# Mayfly_v1p1_revB.net
KiCad netlist of a schematic drawn in EAGLE
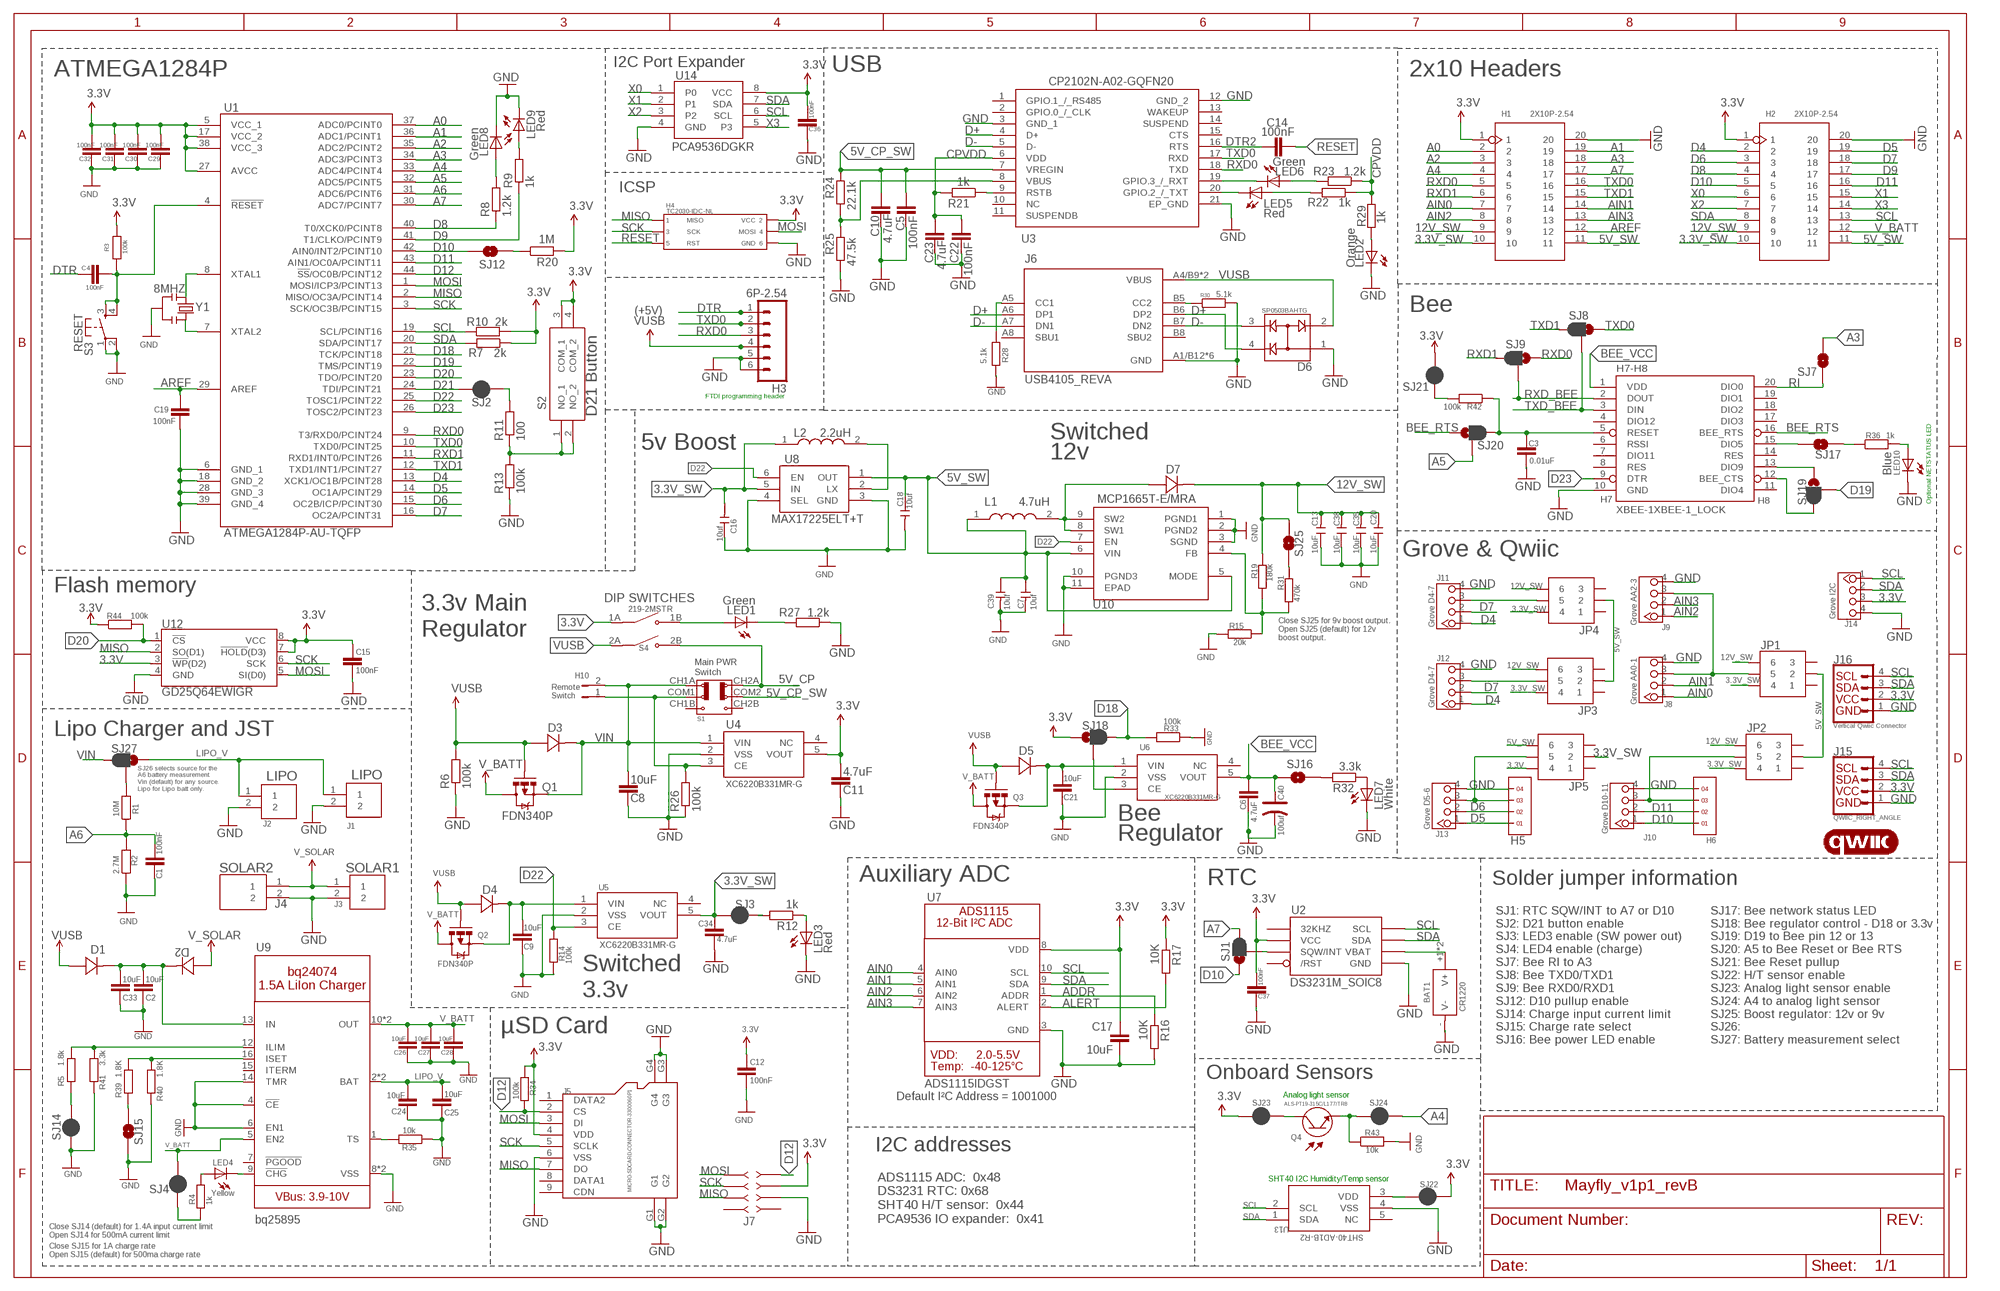
[diagram p0: schematic, sheet 1]

(export (version "E")
  (design (tool "Eeschema 10.0.6"))
  (components
    (comp (ref "BAT1")
      (value "CR1220")
      (footprint "eagle-import:BAT2P-13.5-CR1220")
      (libsource (lib "eagle-import") (part "DIP-BATTERY-CELL-HOLDER(1220)"))
    )
    (comp (ref "C1")
      (value "100nF")
      (footprint "eagle-import:C0603")
      (libsource (lib "eagle-import") (part "C_0603"))
    )
    (comp (ref "C2")
      (value "10uF")
      (footprint "eagle-import:C0603")
      (libsource (lib "eagle-import") (part "C_0603"))
    )
    (comp (ref "C3")
      (value "0.01uF")
      (footprint "eagle-import:C0603")
      (libsource (lib "eagle-import") (part "C_0603"))
    )
    (comp (ref "C4")
      (value "100nF")
      (footprint "eagle-import:C0603")
      (libsource (lib "eagle-import") (part "C_0603"))
    )
    (comp (ref "C5")
      (value "100nF")
      (footprint "eagle-import:C0603")
      (libsource (lib "eagle-import") (part "C_0603"))
    )
    (comp (ref "C6")
      (value "4.7uF")
      (footprint "eagle-import:C0603")
      (libsource (lib "eagle-import") (part "C_0603"))
    )
    (comp (ref "C7")
      (value "10uf")
      (footprint "eagle-import:C0805")
      (fields (field (name "MPN") "CC0805MKX5R5BB226"))
      (libsource (lib "eagle-import") (part "CERAMIC-22UF-6.3V-20%-X5R(0805)"))
    )
    (comp (ref "C8")
      (value "10uF")
      (footprint "eagle-import:C0603")
      (libsource (lib "eagle-import") (part "C_0603"))
    )
    (comp (ref "C9")
      (value "10uF")
      (footprint "eagle-import:C0603")
      (libsource (lib "eagle-import") (part "C_0603"))
    )
    (comp (ref "C10")
      (value "4.7uF")
      (footprint "eagle-import:C0603")
      (libsource (lib "eagle-import") (part "C_0603"))
    )
    (comp (ref "C11")
      (value "4.7uF")
      (footprint "eagle-import:C0603")
      (libsource (lib "eagle-import") (part "C_0603"))
    )
    (comp (ref "C12")
      (value "100nF")
      (footprint "eagle-import:C0603")
      (libsource (lib "eagle-import") (part "C_0603"))
    )
    (comp (ref "C13")
      (value "10uF")
      (footprint "eagle-import:C1206")
      (libsource (lib "eagle-import") (part "CERAMIC-22UF-16V-10%-X7R(1206)"))
    )
    (comp (ref "C14")
      (value "100nF")
      (footprint "eagle-import:C0603")
      (libsource (lib "eagle-import") (part "C_0603"))
    )
    (comp (ref "C15")
      (value "100nF")
      (footprint "eagle-import:C0402")
      (libsource (lib "eagle-import") (part "C_0402"))
    )
    (comp (ref "C16")
      (value "10uf")
      (footprint "eagle-import:C0603")
      (fields (field (name "MPN") "CC0603KRX5R6BB106"))
      (libsource (lib "eagle-import") (part "CERAMIC-10UF-10V-10%-X5R(0603)"))
    )
    (comp (ref "C17")
      (value "10uF")
      (footprint "eagle-import:C0603")
      (libsource (lib "eagle-import") (part "C_0603"))
    )
    (comp (ref "C18")
      (value "10uf")
      (footprint "eagle-import:C0603")
      (fields (field (name "MPN") "CC0603KRX5R6BB106"))
      (libsource (lib "eagle-import") (part "CERAMIC-10UF-10V-10%-X5R(0603)"))
    )
    (comp (ref "C19")
      (value "100nF")
      (footprint "eagle-import:C0402")
      (libsource (lib "eagle-import") (part "C_0402"))
    )
    (comp (ref "C20")
      (value "10uF")
      (footprint "eagle-import:C1206")
      (libsource (lib "eagle-import") (part "CERAMIC-22UF-16V-10%-X7R(1206)"))
    )
    (comp (ref "C21")
      (value "10uF")
      (footprint "eagle-import:C0603")
      (libsource (lib "eagle-import") (part "C_0603"))
    )
    (comp (ref "C22")
      (value "100nF")
      (footprint "eagle-import:C0603")
      (libsource (lib "eagle-import") (part "C_0603"))
    )
    (comp (ref "C23")
      (value "4.7uF")
      (footprint "eagle-import:C0603")
      (libsource (lib "eagle-import") (part "C_0603"))
    )
    (comp (ref "C24")
      (value "10uF")
      (footprint "eagle-import:C0603")
      (libsource (lib "eagle-import") (part "C_0603"))
    )
    (comp (ref "C25")
      (value "10uF")
      (footprint "eagle-import:C0603")
      (libsource (lib "eagle-import") (part "C_0603"))
    )
    (comp (ref "C26")
      (value "10uF")
      (footprint "eagle-import:C0603")
      (libsource (lib "eagle-import") (part "C_0603"))
    )
    (comp (ref "C27")
      (value "10uF")
      (footprint "eagle-import:C0603")
      (libsource (lib "eagle-import") (part "C_0603"))
    )
    (comp (ref "C28")
      (value "10uF")
      (footprint "eagle-import:C0603")
      (libsource (lib "eagle-import") (part "C_0603"))
    )
    (comp (ref "C29")
      (value "100nF")
      (footprint "eagle-import:C0603")
      (libsource (lib "eagle-import") (part "C_0603"))
    )
    (comp (ref "C30")
      (value "100nF")
      (footprint "eagle-import:C0603")
      (libsource (lib "eagle-import") (part "C_0603"))
    )
    (comp (ref "C31")
      (value "100nF")
      (footprint "eagle-import:C0603")
      (libsource (lib "eagle-import") (part "C_0603"))
    )
    (comp (ref "C32")
      (value "100nF")
      (footprint "eagle-import:C0603")
      (libsource (lib "eagle-import") (part "C_0603"))
    )
    (comp (ref "C33")
      (value "10uF")
      (footprint "eagle-import:C0603")
      (libsource (lib "eagle-import") (part "C_0603"))
    )
    (comp (ref "C34")
      (value "4.7uF")
      (footprint "eagle-import:C0603")
      (libsource (lib "eagle-import") (part "C_0603"))
    )
    (comp (ref "C35")
      (value "10uF")
      (footprint "eagle-import:C1206")
      (libsource (lib "eagle-import") (part "CERAMIC-22UF-16V-10%-X7R(1206)"))
    )
    (comp (ref "C36")
      (value "100nF")
      (footprint "eagle-import:C0603")
      (libsource (lib "eagle-import") (part "C_0603"))
    )
    (comp (ref "C37")
      (value "100nF")
      (footprint "eagle-import:C0603")
      (libsource (lib "eagle-import") (part "C_0603"))
    )
    (comp (ref "C38")
      (value "10uF")
      (footprint "eagle-import:C1206")
      (libsource (lib "eagle-import") (part "CERAMIC-22UF-16V-10%-X7R(1206)"))
    )
    (comp (ref "C39")
      (value "10uf")
      (footprint "eagle-import:C0805")
      (fields (field (name "MPN") "CC0805MKX5R5BB226"))
      (libsource (lib "eagle-import") (part "CERAMIC-22UF-6.3V-20%-X5R(0805)"))
    )
    (comp (ref "C40")
      (value "100uf")
      (footprint "eagle-import:AVX-B")
      (fields (field (name "MPN") "TAJB107M010#NJ"))
      (libsource (lib "eagle-import") (part "TANTALUM-SMD-100UF-10V(AVX-B)"))
    )
    (comp (ref "D1")
      (value "MSS2P2-M3/89A")
      (footprint "eagle-import:DIODE_MSP3V3")
      (libsource (lib "eagle-import") (part "MSS2P2-M3/89A"))
    )
    (comp (ref "D2")
      (value "MSS2P2-M3/89A")
      (footprint "eagle-import:DIODE_MSP3V3")
      (libsource (lib "eagle-import") (part "MSS2P2-M3/89A"))
    )
    (comp (ref "D3")
      (value "MSS2P2-M3/89A")
      (footprint "eagle-import:DIODE_MSP3V3")
      (libsource (lib "eagle-import") (part "MSS2P2-M3/89A"))
    )
    (comp (ref "D4")
      (value "MSS2P2-M3/89A")
      (footprint "eagle-import:DIODE_MSP3V3")
      (libsource (lib "eagle-import") (part "MSS2P2-M3/89A"))
    )
    (comp (ref "D5")
      (value "MSS2P2-M3/89A")
      (footprint "eagle-import:DIODE_MSP3V3")
      (libsource (lib "eagle-import") (part "MSS2P2-M3/89A"))
    )
    (comp (ref "D6")
      (value "SP0503BAHTG")
      (footprint "eagle-import:SOT143")
      (fields (field (name "DIGI-KEY_PART_NUMBER") "F2715CT-ND") (field (name "MF") "Littelfuse Inc."))
      (libsource (lib "eagle-import") (part "SP0503BAHTG"))
    )
    (comp (ref "D7")
      (value "MSS2P2-M3/89A")
      (footprint "eagle-import:DIODE_MSP3V3")
      (libsource (lib "eagle-import") (part "MSS2P2-M3/89A"))
    )
    (comp (ref "H1")
      (value "2X10P-2.54")
      (footprint "eagle-import:H2X10-2.54")
      (fields (field (name "MPN") "F185-1210A0BA1"))
      (libsource (lib "eagle-import") (part "DIP-BLACK-FEMALE-HEADER(2X10P-2.54)-2.54"))
    )
    (comp (ref "H2")
      (value "2X10P-2.54")
      (footprint "eagle-import:H2X10-2.54")
      (fields (field (name "MPN") "F185-1210A0BA1"))
      (libsource (lib "eagle-import") (part "DIP-BLACK-FEMALE-HEADER(2X10P-2.54)-2.54"))
    )
    (comp (ref "H3")
      (value "6P-2.54")
      (footprint "eagle-import:1X06_FEMALE_LOCK.010")
      (libsource (lib "eagle-import") (part "M06FEMALE_LOCK"))
    )
    (comp (ref "H4")
      (value "TC2030-IDC-NL")
      (footprint "eagle-import:TC2030-IDC-NL")
      (fields
        (field (name "HOUSEPART") "NO")
        (field (name "LABEL01") "MISO")
        (field (name "LABEL02") "VCC")
        (field (name "LABEL03") "SCK")
        (field (name "LABEL04") "MOSI")
        (field (name "LABEL05") "RST")
        (field (name "LABEL06") "GND")
      )
      (libsource (lib "eagle-import") (part "CON_02X03_TC2030-IDC-NL_AVRISP"))
    )
    (comp (ref "H5")
      (value "1X4")
      (footprint "eagle-import:1X4")
      (libsource (lib "eagle-import") (part "1X4"))
    )
    (comp (ref "H6")
      (value "1X4")
      (footprint "eagle-import:1X4")
      (libsource (lib "eagle-import") (part "1X4"))
    )
    (comp (ref "H7-H8")
      (value "XBEE-1XBEE-1_LOCK")
      (footprint "eagle-import:XBEE-1_LOCK")
      (libsource (lib "eagle-import") (part "XBEE-1XBEE-1_LOCK"))
    )
    (comp (ref "H10")
      (value "JUMPER-PTH-2-NO")
      (footprint "eagle-import:PTH-JUMPER-2-NO_NO_SILK")
      (libsource (lib "eagle-import") (part "JUMPER-PTH-2-NO"))
    )
    (comp (ref "J1")
      (value "JST_EPH_2PIN")
      (footprint "eagle-import:JST_EPH_B2B-PH-K-S")
      (libsource (lib "eagle-import") (part "JST_EPH_2PIN"))
    )
    (comp (ref "J2")
      (value "JST_EPH_2PIN")
      (footprint "eagle-import:JST_EPH_B2B-PH-K-S")
      (libsource (lib "eagle-import") (part "JST_EPH_2PIN"))
    )
    (comp (ref "J3")
      (value "JST_EPH_2PIN")
      (footprint "eagle-import:JST_EPH_B2B-PH-K-S")
      (libsource (lib "eagle-import") (part "JST_EPH_2PIN"))
    )
    (comp (ref "J4")
      (value "1778557")
      (footprint "eagle-import:SHDR2W70P0X250_1X2_670X500X765")
      (fields (field (name "MOUSER_PART_NUMBER") "651-1778557"))
      (libsource (lib "eagle-import") (part "1778557"))
    )
    (comp (ref "J5")
      (value "MICRO-SDCARD-CONNECTOR-3300060P1")
      (footprint "eagle-import:9P-SMD-W-RING")
      (libsource (lib "eagle-import") (part "MICRO-SDCARD-CONNECTOR-3300060P1"))
    )
    (comp (ref "J6")
      (value "USB4105_REVA")
      (footprint "eagle-import:GCT_USB4105_REVA")
      (fields (field (name "MF") "Global Connector Technology") (field (name "MP") "USB4105"))
      (libsource (lib "eagle-import") (part "USB4105_REVA"))
    )
    (comp (ref "J7")
      (value "79107-08_S")
      (footprint "eagle-import:79107-08")
      (libsource (lib "eagle-import") (part "79107-08_S"))
    )
    (comp (ref "J8")
      (value "Grove AA0-1")
      (footprint "eagle-import:HW4-2.0")
      (libsource (lib "eagle-import") (part "GROVE-CONNECTOR-DIP(4P-2.0)"))
    )
    (comp (ref "J9")
      (value "Grove AA2-3")
      (footprint "eagle-import:HW4-2.0")
      (libsource (lib "eagle-import") (part "GROVE-CONNECTOR-DIP(4P-2.0)"))
    )
    (comp (ref "J10")
      (value "Grove D10-11")
      (footprint "eagle-import:HW4-2.0")
      (libsource (lib "eagle-import") (part "GROVE-CONNECTOR-DIP(4P-2.0)"))
    )
    (comp (ref "J11")
      (value "Grove D4-7")
      (footprint "eagle-import:HW4-2.0")
      (libsource (lib "eagle-import") (part "GROVE-CONNECTOR-DIP(4P-2.0)"))
    )
    (comp (ref "J12")
      (value "Grove D4-7")
      (footprint "eagle-import:HW4-2.0")
      (libsource (lib "eagle-import") (part "GROVE-CONNECTOR-DIP(4P-2.0)"))
    )
    (comp (ref "J13")
      (value "Grove D5-6")
      (footprint "eagle-import:HW4-2.0")
      (libsource (lib "eagle-import") (part "GROVE-CONNECTOR-DIP(4P-2.0)"))
    )
    (comp (ref "J14")
      (value "Grove I2C")
      (footprint "eagle-import:HW4-2.0")
      (libsource (lib "eagle-import") (part "GROVE-CONNECTOR-DIP(4P-2.0)"))
    )
    (comp (ref "J15")
      (value "QWIIC_RIGHT_ANGLE")
      (footprint "eagle-import:JST04_1MM_RA")
      (libsource (lib "eagle-import") (part "QWIIC_CONNECTORJS-1MM"))
    )
    (comp (ref "J16")
      (value "Vertical Qwiic Connector")
      (footprint "eagle-import:JST04_1MM_VERT")
      (libsource (lib "eagle-import") (part "QWIIC_CONNECTOR"))
    )
    (comp (ref "JP1")
      (value "M22-2520305")
      (footprint "eagle-import:HDRV6W50P200_2X3_600X400X525P")
      (fields (field (name "MOUSER_PART_NUMBER") "855-M22-2520305"))
      (libsource (lib "eagle-import") (part "M22-2520305"))
    )
    (comp (ref "JP2")
      (value "M22-2520305")
      (footprint "eagle-import:HDRV6W50P200_2X3_600X400X525P")
      (fields (field (name "MOUSER_PART_NUMBER") "855-M22-2520305"))
      (libsource (lib "eagle-import") (part "M22-2520305"))
    )
    (comp (ref "JP3")
      (value "M22-2520305")
      (footprint "eagle-import:HDRV6W50P200_2X3_600X400X525P")
      (fields (field (name "MOUSER_PART_NUMBER") "855-M22-2520305"))
      (libsource (lib "eagle-import") (part "M22-2520305"))
    )
    (comp (ref "JP4")
      (value "M22-2520305")
      (footprint "eagle-import:HDRV6W50P200_2X3_600X400X525P")
      (fields (field (name "MOUSER_PART_NUMBER") "855-M22-2520305"))
      (libsource (lib "eagle-import") (part "M22-2520305"))
    )
    (comp (ref "JP5")
      (value "M22-2520305")
      (footprint "eagle-import:HDRV6W50P200_2X3_600X400X525P")
      (fields (field (name "MOUSER_PART_NUMBER") "855-M22-2520305"))
      (libsource (lib "eagle-import") (part "M22-2520305"))
    )
    (comp (ref "L1")
      (value "4.7uH")
      (footprint "eagle-import:XAL4030472MEC")
      (fields
        (field (name "MANUFACTURER_PART_NUMBER") "XAL4030-472MEC")
        (field (name "MOUSER_PART_NUMBER") "994-XAL4030-472MEC")
      )
      (libsource (lib "eagle-import") (part "XAL4030-472MEC"))
    )
    (comp (ref "L2")
      (value "2.2uH")
      (footprint "eagle-import:1285ASH1R0MP2")
      (fields
        (field (name "MANUFACTURER_PART_NUMBER") "DFE201610E-2R2M=P2")
        (field (name "MOUSER_PART_NUMBER") "81-DFE201610E-2R2MP2")
      )
      (libsource (lib "eagle-import") (part "DFE201610E-2R2M=P2"))
    )
    (comp (ref "LED1")
      (value "Green")
      (footprint "eagle-import:LED-0603")
      (libsource (lib "eagle-import") (part "LED0603"))
    )
    (comp (ref "LED2")
      (value "Orange")
      (footprint "eagle-import:LED-0603")
      (libsource (lib "eagle-import") (part "LED0603"))
    )
    (comp (ref "LED3")
      (value "Red")
      (footprint "eagle-import:LED-0603")
      (libsource (lib "eagle-import") (part "LED0603"))
    )
    (comp (ref "LED4")
      (value "Yellow")
      (footprint "eagle-import:LED-0603")
      (libsource (lib "eagle-import") (part "LED0603"))
    )
    (comp (ref "LED5")
      (value "Red")
      (footprint "eagle-import:LED-0603")
      (libsource (lib "eagle-import") (part "LED0603"))
    )
    (comp (ref "LED6")
      (value "Green")
      (footprint "eagle-import:LED-0603")
      (libsource (lib "eagle-import") (part "LED0603"))
    )
    (comp (ref "LED7")
      (value "White")
      (footprint "eagle-import:LED-0603")
      (libsource (lib "eagle-import") (part "LED0603"))
    )
    (comp (ref "LED8")
      (value "Green")
      (footprint "eagle-import:LED-0603")
      (libsource (lib "eagle-import") (part "LED0603"))
    )
    (comp (ref "LED9")
      (value "Red")
      (footprint "eagle-import:LED-0603")
      (libsource (lib "eagle-import") (part "LED0603"))
    )
    (comp (ref "LED10")
      (value "Blue")
      (footprint "eagle-import:LED-0603")
      (libsource (lib "eagle-import") (part "LED0603"))
    )
    (comp (ref "LOGO4")
      (value "QWIIC_LOGO_5MM")
      (footprint "eagle-import:QWIIC_5MM")
      (libsource (lib "eagle-import") (part "QWIIC_LOGO_5MM"))
    )
    (comp (ref "Q1")
      (value "FDN340P")
      (footprint "eagle-import:SOT23-S-PADS")
      (libsource (lib "eagle-import") (part "MOSFET-P-CHANNELSMALL"))
    )
    (comp (ref "Q2")
      (value "FDN340P")
      (footprint "eagle-import:SOT23-S-PADS")
      (libsource (lib "eagle-import") (part "MOSFET-P-CHANNELSMALL"))
    )
    (comp (ref "Q3")
      (value "FDN340P")
      (footprint "eagle-import:SOT23-S-PADS")
      (libsource (lib "eagle-import") (part "MOSFET-P-CHANNELSMALL"))
    )
    (comp (ref "Q4")
      (value "ALS-PT19-315C/L177/TR8")
      (footprint "eagle-import:XDCR_ALS-PT19-315C_L177_TR8")
      (fields (field (name "MF") "Everlight"))
      (libsource (lib "eagle-import") (part "ALS-PT19-315C/L177/TR8"))
    )
    (comp (ref "R1")
      (value "10M")
      (footprint "eagle-import:R0402")
      (libsource (lib "eagle-import") (part "R_0402"))
    )
    (comp (ref "R2")
      (value "2.7M")
      (footprint "eagle-import:R0402")
      (libsource (lib "eagle-import") (part "R_0402"))
    )
    (comp (ref "R3")
      (value "100k")
      (footprint "eagle-import:R0603")
      (libsource (lib "eagle-import") (part "R_0603"))
    )
    (comp (ref "R4")
      (value "1k")
      (footprint "eagle-import:R0402")
      (libsource (lib "eagle-import") (part "R_0402"))
    )
    (comp (ref "R5")
      (value "1.8k")
      (footprint "eagle-import:R0402")
      (libsource (lib "eagle-import") (part "R_0402"))
    )
    (comp (ref "R6")
      (value "100k")
      (footprint "eagle-import:R0402")
      (libsource (lib "eagle-import") (part "R_0402"))
    )
    (comp (ref "R7")
      (value "2k")
      (footprint "eagle-import:R0603")
      (libsource (lib "eagle-import") (part "R_0603"))
    )
    (comp (ref "R8")
      (value "1.2k")
      (footprint "eagle-import:R0402")
      (libsource (lib "eagle-import") (part "R_0402"))
    )
    (comp (ref "R9")
      (value "1k")
      (footprint "eagle-import:R0402")
      (libsource (lib "eagle-import") (part "R_0402"))
    )
    (comp (ref "R10")
      (value "2k")
      (footprint "eagle-import:R0603")
      (libsource (lib "eagle-import") (part "R_0603"))
    )
    (comp (ref "R11")
      (value "100")
      (footprint "eagle-import:R0402")
      (libsource (lib "eagle-import") (part "R_0402"))
    )
    (comp (ref "R12")
      (value "1k")
      (footprint "eagle-import:R0402")
      (libsource (lib "eagle-import") (part "R_0402"))
    )
    (comp (ref "R13")
      (value "100k")
      (footprint "eagle-import:R0402")
      (libsource (lib "eagle-import") (part "R_0402"))
    )
    (comp (ref "R14")
      (value "100k")
      (footprint "eagle-import:R0402")
      (libsource (lib "eagle-import") (part "R_0402"))
    )
    (comp (ref "R15")
      (value "20k")
      (footprint "eagle-import:R0402")
      (libsource (lib "eagle-import") (part "R_0402"))
    )
    (comp (ref "R16")
      (value "10K")
      (footprint "eagle-import:R0402")
      (libsource (lib "eagle-import") (part "R_0402"))
    )
    (comp (ref "R17")
      (value "10K")
      (footprint "eagle-import:R0402")
      (libsource (lib "eagle-import") (part "R_0402"))
    )
    (comp (ref "R19")
      (value "180k")
      (footprint "eagle-import:R0402")
      (libsource (lib "eagle-import") (part "R_0402"))
    )
    (comp (ref "R20")
      (value "1M")
      (footprint "eagle-import:R0603")
      (libsource (lib "eagle-import") (part "R_0603"))
    )
    (comp (ref "R21")
      (value "1k")
      (footprint "eagle-import:R0402")
      (libsource (lib "eagle-import") (part "R_0402"))
    )
    (comp (ref "R22")
      (value "1k")
      (footprint "eagle-import:R0402")
      (libsource (lib "eagle-import") (part "R_0402"))
    )
    (comp (ref "R23")
      (value "1.2k")
      (footprint "eagle-import:R0402")
      (libsource (lib "eagle-import") (part "R_0402"))
    )
    (comp (ref "R24")
      (value "22.1k")
      (footprint "eagle-import:R0402")
      (libsource (lib "eagle-import") (part "R_0402"))
    )
    (comp (ref "R25")
      (value "47.5k")
      (footprint "eagle-import:R0402")
      (libsource (lib "eagle-import") (part "R_0402"))
    )
    (comp (ref "R26")
      (value "100k")
      (footprint "eagle-import:R0603")
      (libsource (lib "eagle-import") (part "R_0603"))
    )
    (comp (ref "R27")
      (value "1.2k")
      (footprint "eagle-import:R0402")
      (libsource (lib "eagle-import") (part "R_0402"))
    )
    (comp (ref "R28")
      (value "5.1k")
      (footprint "eagle-import:R0402")
      (libsource (lib "eagle-import") (part "R_0402"))
    )
    (comp (ref "R29")
      (value "1k")
      (footprint "eagle-import:R0402")
      (libsource (lib "eagle-import") (part "R_0402"))
    )
    (comp (ref "R30")
      (value "5.1k")
      (footprint "eagle-import:R0402")
      (libsource (lib "eagle-import") (part "R_0402"))
    )
    (comp (ref "R31")
      (value "470k")
      (footprint "eagle-import:R0402")
      (libsource (lib "eagle-import") (part "R_0402"))
    )
    (comp (ref "R32")
      (value "3.3k")
      (footprint "eagle-import:R0402")
      (libsource (lib "eagle-import") (part "R_0402"))
    )
    (comp (ref "R33")
      (value "100k")
      (footprint "eagle-import:R0402")
      (libsource (lib "eagle-import") (part "R_0402"))
    )
    (comp (ref "R34")
      (value "100k")
      (footprint "eagle-import:R0402")
      (libsource (lib "eagle-import") (part "R_0402"))
    )
    (comp (ref "R35")
      (value "10k")
      (footprint "eagle-import:R0402")
      (libsource (lib "eagle-import") (part "R_0402"))
    )
    (comp (ref "R36")
      (value "1k")
      (footprint "eagle-import:R0402")
      (libsource (lib "eagle-import") (part "R_0402"))
    )
    (comp (ref "R39")
      (value "1.8K")
      (footprint "eagle-import:R0402")
      (libsource (lib "eagle-import") (part "R_0402"))
    )
    (comp (ref "R40")
      (value "1.8K")
      (footprint "eagle-import:R0402")
      (libsource (lib "eagle-import") (part "R_0402"))
    )
    (comp (ref "R41")
      (value "3.3k")
      (footprint "eagle-import:R0402")
      (libsource (lib "eagle-import") (part "R_0402"))
    )
    (comp (ref "R42")
      (value "100k")
      (footprint "eagle-import:R0402")
      (libsource (lib "eagle-import") (part "R_0402"))
    )
    (comp (ref "R43")
      (value "10k")
      (footprint "eagle-import:R0402")
      (libsource (lib "eagle-import") (part "R_0402"))
    )
    (comp (ref "R44")
      (value "100k")
      (footprint "eagle-import:R0402")
      (libsource (lib "eagle-import") (part "R_0402"))
    )
    (comp (ref "S1")
      (value "SWITCH-2CH-6P-3010010P1")
      (footprint "eagle-import:6P-2CH-2.54-9.1X3.5X3.2+2H")
      (libsource (lib "eagle-import") (part "SWITCH-2CH-6P-3010010P1"))
    )
    (comp (ref "S2")
      (value "PTS647SK38SMTR2LFS")
      (footprint "eagle-import:PTS647SK38SMTR2LFS")
      (fields (field (name "MOUSER_PART_NUMBER") "611-PTS647SK38SMTR2L"))
      (libsource (lib "eagle-import") (part "PTS647SK38SMTR2LFS"))
    )
    (comp (ref "S3")
      (value "MOMENTARY-SWITCH-SPST-2-SMD-4.6X2.8MM")
      (footprint "eagle-import:TACTILE_SWITCH_SMD_4.6X2.8MM")
      (libsource (lib "eagle-import") (part "MOMENTARY-SWITCH-SPST-2-SMD-4.6X2.8MM"))
    )
    (comp (ref "S4")
      (value "219-2MSTR")
      (footprint "eagle-import:SW_219-2MSTR")
      (fields (field (name "DIGI-KEY_PART_NUMBER") "CT3114CT-ND") (field (name "MF") "CTS Electrocomponents"))
      (libsource (lib "eagle-import") (part "219-2MSTR"))
    )
    (comp (ref "SJ1")
      (value "JUMPER-SMT_3_1-NC_PASTE_SILK")
      (footprint "eagle-import:SMT-JUMPER_3_1-NC_PASTE_SILK")
      (libsource (lib "eagle-import") (part "JUMPER-SMT_3_1-NC_PASTE_SILK"))
    )
    (comp (ref "SJ2")
      (value "JUMPER-SMT_2_NC_PASTE_SILK")
      (footprint "eagle-import:SMT-JUMPER_2_NC_PASTE_SILK")
      (libsource (lib "eagle-import") (part "JUMPER-SMT_2_NC_PASTE_SILK"))
    )
    (comp (ref "SJ3")
      (value "JUMPER-SMT_2_NC_PASTE_SILK")
      (footprint "eagle-import:SMT-JUMPER_2_NC_PASTE_SILK")
      (libsource (lib "eagle-import") (part "JUMPER-SMT_2_NC_PASTE_SILK"))
    )
    (comp (ref "SJ4")
      (value "JUMPER-SMT_2_NC_PASTE_SILK")
      (footprint "eagle-import:SMT-JUMPER_2_NC_PASTE_SILK")
      (libsource (lib "eagle-import") (part "JUMPER-SMT_2_NC_PASTE_SILK"))
    )
    (comp (ref "SJ7")
      (value "JUMPER-SMT_2_NO_SILK")
      (footprint "eagle-import:SMT-JUMPER_2_NO_SILK")
      (libsource (lib "eagle-import") (part "JUMPER-SMT_2_NO_SILK"))
    )
    (comp (ref "SJ8")
      (value "JUMPER-SMT_3_1-NC_PASTE_SILK")
      (footprint "eagle-import:SMT-JUMPER_3_1-NC_PASTE_SILK")
      (libsource (lib "eagle-import") (part "JUMPER-SMT_3_1-NC_PASTE_SILK"))
    )
    (comp (ref "SJ9")
      (value "JUMPER-SMT_3_1-NC_PASTE_SILK")
      (footprint "eagle-import:SMT-JUMPER_3_1-NC_PASTE_SILK")
      (libsource (lib "eagle-import") (part "JUMPER-SMT_3_1-NC_PASTE_SILK"))
    )
    (comp (ref "SJ12")
      (value "SOLDERJUMPERNO")
      (footprint "eagle-import:SJ_2S-NO")
      (libsource (lib "eagle-import") (part "SOLDERJUMPERNO"))
    )
    (comp (ref "SJ14")
      (value "JUMPER-SMT_2_NC_PASTE_SILK")
      (footprint "eagle-import:SMT-JUMPER_2_NC_PASTE_SILK")
      (libsource (lib "eagle-import") (part "JUMPER-SMT_2_NC_PASTE_SILK"))
    )
    (comp (ref "SJ15")
      (value "JUMPER-SMT_2_NO_SILK")
      (footprint "eagle-import:SMT-JUMPER_2_NO_SILK")
      (libsource (lib "eagle-import") (part "JUMPER-SMT_2_NO_SILK"))
    )
    (comp (ref "SJ16")
      (value "JUMPER-SMT_2_NO_SILK")
      (footprint "eagle-import:SMT-JUMPER_2_NO_SILK")
      (libsource (lib "eagle-import") (part "JUMPER-SMT_2_NO_SILK"))
    )
    (comp (ref "SJ17")
      (value "JUMPER-SMT_2_NO_SILK")
      (footprint "eagle-import:SMT-JUMPER_2_NO_SILK")
      (libsource (lib "eagle-import") (part "JUMPER-SMT_2_NO_SILK"))
    )
    (comp (ref "SJ18")
      (value "JUMPER-SMT_3_1-NC_PASTE_SILK")
      (footprint "eagle-import:SMT-JUMPER_3_1-NC_PASTE_SILK")
      (libsource (lib "eagle-import") (part "JUMPER-SMT_3_1-NC_PASTE_SILK"))
    )
    (comp (ref "SJ19")
      (value "JUMPER-SMT_3_1-NC_PASTE_SILK")
      (footprint "eagle-import:SMT-JUMPER_3_1-NC_PASTE_SILK")
      (libsource (lib "eagle-import") (part "JUMPER-SMT_3_1-NC_PASTE_SILK"))
    )
    (comp (ref "SJ20")
      (value "JUMPER-SMT_3_1-NC_PASTE_SILK")
      (footprint "eagle-import:SMT-JUMPER_3_1-NC_PASTE_SILK")
      (libsource (lib "eagle-import") (part "JUMPER-SMT_3_1-NC_PASTE_SILK"))
    )
    (comp (ref "SJ21")
      (value "JUMPER-SMT_2_NC_PASTE_SILK")
      (footprint "eagle-import:SMT-JUMPER_2_NC_PASTE_SILK")
      (libsource (lib "eagle-import") (part "JUMPER-SMT_2_NC_PASTE_SILK"))
    )
    (comp (ref "SJ22")
      (value "JUMPER-SMT_2_NC_PASTE_SILK")
      (footprint "eagle-import:SMT-JUMPER_2_NC_PASTE_SILK")
      (libsource (lib "eagle-import") (part "JUMPER-SMT_2_NC_PASTE_SILK"))
    )
    (comp (ref "SJ23")
      (value "JUMPER-SMT_2_NC_PASTE_SILK")
      (footprint "eagle-import:SMT-JUMPER_2_NC_PASTE_SILK")
      (libsource (lib "eagle-import") (part "JUMPER-SMT_2_NC_PASTE_SILK"))
    )
    (comp (ref "SJ24")
      (value "JUMPER-SMT_2_NC_PASTE_SILK")
      (footprint "eagle-import:SMT-JUMPER_2_NC_PASTE_SILK")
      (libsource (lib "eagle-import") (part "JUMPER-SMT_2_NC_PASTE_SILK"))
    )
    (comp (ref "SJ25")
      (value "JUMPER-SMT_2_NO_SILK")
      (footprint "eagle-import:SMT-JUMPER_2_NO_SILK")
      (libsource (lib "eagle-import") (part "JUMPER-SMT_2_NO_SILK"))
    )
    (comp (ref "SJ27")
      (value "JUMPER-SMT_3_1-NC_PASTE_SILK")
      (footprint "eagle-import:SMT-JUMPER_3_1-NC_PASTE_SILK")
      (libsource (lib "eagle-import") (part "JUMPER-SMT_3_1-NC_PASTE_SILK"))
    )
    (comp (ref "U1")
      (value "ATMEGA1284P-AU-TQFP")
      (footprint "eagle-import:QFP80P1200X1200X120-44N")
      (fields
        (field (name "MANUFACTURER_PART_NUMBER") "ATMEGA1284P-AU")
        (field (name "MOUSER_PART_NUMBER") "556-ATMEGA1284P-AU")
      )
      (libsource (lib "eagle-import") (part "ATMEGA1284P-AU-TQFP"))
    )
    (comp (ref "U2")
      (value "DS3231M_SOIC8")
      (footprint "eagle-import:SO8")
      (libsource (lib "eagle-import") (part "DS3231M_SOIC8"))
    )
    (comp (ref "U3")
      (value "CP2102N-A02-GQFN20")
      (footprint "eagle-import:CP2102NA02GQFN20")
      (fields (field (name "MOUSER_PART_NUMBER") "634-CP2102NA02GQFN20"))
      (libsource (lib "eagle-import") (part "CP2102N-A02-GQFN20"))
    )
    (comp (ref "U4")
      (value "XC6220B331MR-G")
      (footprint "eagle-import:SOT95P280X130-5N")
      (fields (field (name "MOUSER_PART_NUMBER") "865-XC6220B331MR-G"))
      (libsource (lib "eagle-import") (part "XC6220B331MR-G"))
    )
    (comp (ref "U5")
      (value "XC6220B331MR-G")
      (footprint "eagle-import:SOT95P280X130-5N")
      (fields (field (name "MOUSER_PART_NUMBER") "865-XC6220B331MR-G"))
      (libsource (lib "eagle-import") (part "XC6220B331MR-G"))
    )
    (comp (ref "U6")
      (value "XC6220B331MR-G")
      (footprint "eagle-import:SOT95P280X130-5N")
      (fields (field (name "MOUSER_PART_NUMBER") "865-XC6220B331MR-G"))
      (libsource (lib "eagle-import") (part "XC6220B331MR-G"))
    )
    (comp (ref "U7")
      (value "ADS1115IDGST")
      (footprint "eagle-import:MSOP10")
      (libsource (lib "eagle-import") (part "ADC_ADS1015"))
    )
    (comp (ref "U8")
      (value "MAX17225ELT+T")
      (footprint "eagle-import:MAX17225ELTT")
      (fields (field (name "MOUSER_PART_NUMBER") "700-MAX17225ELT+T"))
      (libsource (lib "eagle-import") (part "MAX17225ELT+T"))
    )
    (comp (ref "U9")
      (value "ADAFRUIT_POWER_BQ24074")
      (footprint "eagle-import:ADAFRUIT_POWER_QFN16_3MM")
      (libsource (lib "eagle-import") (part "ADAFRUIT_POWER_BQ24074"))
    )
    (comp (ref "U10")
      (value "MCP1665T-E/MRA")
      (footprint "eagle-import:QFN50P200X200X90-11N")
      (libsource (lib "eagle-import") (part "MCP1665T-E/MRA"))
    )
    (comp (ref "U12")
      (value "GD25Q64EWIGR")
      (footprint "eagle-import:WSON8-6X5MM")
      (libsource (lib "eagle-import") (part "W25Q32FVZP"))
    )
    (comp (ref "U13")
      (value "SHT40-AD1B-R2")
      (footprint "eagle-import:SHT4X_SEN")
      (fields (field (name "COPYRIGHT") "Copyright (C) 2018 Accelerated Designs. All rights reserved"))
      (libsource (lib "eagle-import") (part "SHT40-AD1B-R2"))
    )
    (comp (ref "U14")
      (value "PCA9536DGKR")
      (footprint "eagle-import:SOP65P490X110-8N")
      (fields (field (name "MOUSER_PART_NUMBER") "595-PCA9536DGKR"))
      (libsource (lib "eagle-import") (part "PCA9536DGKR"))
    )
    (comp (ref "Y1")
      (value "8MHZ")
      (footprint "eagle-import:X3-SMD-3.6X1.3X0.8MM")
      (fields (field (name "MPN") "CSTCE8M00G15L99-R0"))
      (libsource (lib "eagle-import") (part "SMD-RESONATOR-8MHZ-33PF-0.1%(3P-3.2X1.3MM)"))
    )
  )
  (nets
    (net (code "1") (name "/5V_CP") (class "Default")
      (node (ref "S1") (pin "CH2A") (pinfunction "CH2A_CH2A") (pintype "bidirectional"))
      (node (ref "S4") (pin "2B") (pinfunction "NO2_2B") (pintype "passive"))
    )
    (net (code "2") (name "/A0") (class "Default")
      (node (ref "H1") (pin "2") (pinfunction "2_2") (pintype "bidirectional"))
      (node (ref "U1") (pin "37") (pinfunction "ADC0/PCINT0_37") (pintype "bidirectional"))
    )
    (net (code "3") (name "/A1") (class "Default")
      (node (ref "H1") (pin "19") (pinfunction "19_19") (pintype "bidirectional"))
      (node (ref "U1") (pin "36") (pinfunction "ADC1/PCINT1_36") (pintype "bidirectional"))
    )
    (net (code "4") (name "/A2") (class "Default")
      (node (ref "H1") (pin "3") (pinfunction "3_3") (pintype "bidirectional"))
      (node (ref "U1") (pin "35") (pinfunction "ADC2/PCINT2_35") (pintype "bidirectional"))
    )
    (net (code "5") (name "/ADDR") (class "Default")
      (node (ref "R16") (pin "1") (pinfunction "1_1") (pintype "passive"))
      (node (ref "U7") (pin "1") (pinfunction "ADDR_1") (pintype "bidirectional"))
    )
    (net (code "6") (name "/AIN0") (class "Default")
      (node (ref "H1") (pin "7") (pinfunction "7_7") (pintype "bidirectional"))
      (node (ref "J8") (pin "1") (pinfunction "1_1") (pintype "bidirectional"))
      (node (ref "U7") (pin "4") (pinfunction "AIN0_4") (pintype "bidirectional"))
    )
    (net (code "7") (name "/AIN1") (class "Default")
      (node (ref "H1") (pin "14") (pinfunction "14_14") (pintype "bidirectional"))
      (node (ref "J8") (pin "2") (pinfunction "2_2") (pintype "bidirectional"))
      (node (ref "U7") (pin "5") (pinfunction "AIN1_5") (pintype "bidirectional"))
    )
    (net (code "8") (name "/AIN2") (class "Default")
      (node (ref "H1") (pin "8") (pinfunction "8_8") (pintype "bidirectional"))
      (node (ref "J9") (pin "1") (pinfunction "1_1") (pintype "bidirectional"))
      (node (ref "U7") (pin "6") (pinfunction "AIN2_6") (pintype "bidirectional"))
    )
    (net (code "9") (name "/AIN3") (class "Default")
      (node (ref "H1") (pin "13") (pinfunction "13_13") (pintype "bidirectional"))
      (node (ref "J9") (pin "2") (pinfunction "2_2") (pintype "bidirectional"))
      (node (ref "U7") (pin "7") (pinfunction "AIN3_7") (pintype "bidirectional"))
    )
    (net (code "10") (name "/ALERT") (class "Default")
      (node (ref "R17") (pin "2") (pinfunction "2_2") (pintype "passive"))
      (node (ref "U7") (pin "2") (pinfunction "ALERT_2") (pintype "bidirectional"))
    )
    (net (code "11") (name "/AREF") (class "Default")
      (node (ref "C19") (pin "2") (pinfunction "2_2") (pintype "passive"))
      (node (ref "H1") (pin "12") (pinfunction "12_12") (pintype "bidirectional"))
      (node (ref "U1") (pin "29") (pinfunction "AREF_29") (pintype "bidirectional"))
    )
    (net (code "12") (name "/BEE_RTS") (class "Default")
      (node (ref "H7-H8") (pin "16") (pinfunction "BEE_RTS_16") (pintype "input"))
      (node (ref "SJ20") (pin "1") (pinfunction "1_1") (pintype "passive"))
    )
    (net (code "13") (name "/CPVDD") (class "Default")
      (node (ref "C22") (pin "2") (pinfunction "2_2") (pintype "passive"))
      (node (ref "C23") (pin "2") (pinfunction "2_2") (pintype "passive"))
      (node (ref "R21") (pin "2") (pinfunction "2_2") (pintype "passive"))
      (node (ref "R22") (pin "1") (pinfunction "1_1") (pintype "passive"))
      (node (ref "R23") (pin "1") (pinfunction "1_1") (pintype "passive"))
      (node (ref "R29") (pin "1") (pinfunction "1_1") (pintype "passive"))
      (node (ref "U3") (pin "6") (pinfunction "VDD_6") (pintype "bidirectional"))
    )
    (net (code "14") (name "/D+") (class "Default")
      (node (ref "D6") (pin "4") (pinfunction "4_4") (pintype "passive"))
      (node (ref "J6") (pin "A6") (pinfunction "DP1_A6") (pintype "bidirectional"))
      (node (ref "J6") (pin "B6") (pinfunction "DP2_B6") (pintype "bidirectional"))
      (node (ref "U3") (pin "4") (pinfunction "D+_4") (pintype "bidirectional"))
    )
    (net (code "15") (name "/D-") (class "Default")
      (node (ref "D6") (pin "3") (pinfunction "3_3") (pintype "passive"))
      (node (ref "J6") (pin "A7") (pinfunction "DN1_A7") (pintype "bidirectional"))
      (node (ref "J6") (pin "B7") (pinfunction "DN2_B7") (pintype "bidirectional"))
      (node (ref "U3") (pin "5") (pinfunction "D-_5") (pintype "bidirectional"))
    )
    (net (code "16") (name "/D4") (class "Default")
      (node (ref "H2") (pin "2") (pinfunction "2_2") (pintype "bidirectional"))
      (node (ref "J11") (pin "1") (pinfunction "1_1") (pintype "bidirectional"))
      (node (ref "J12") (pin "1") (pinfunction "1_1") (pintype "bidirectional"))
      (node (ref "U1") (pin "13") (pinfunction "XCK1/OC1B/PCINT28_13") (pintype "bidirectional"))
    )
    (net (code "17") (name "/D5") (class "Default")
      (node (ref "H2") (pin "19") (pinfunction "19_19") (pintype "bidirectional"))
      (node (ref "H5") (pin "1") (pinfunction "1_1") (pintype "bidirectional"))
      (node (ref "J13") (pin "1") (pinfunction "1_1") (pintype "bidirectional"))
      (node (ref "U1") (pin "14") (pinfunction "OC1A/PCINT29_14") (pintype "bidirectional"))
    )
    (net (code "18") (name "/D6") (class "Default")
      (node (ref "H2") (pin "3") (pinfunction "3_3") (pintype "bidirectional"))
      (node (ref "H5") (pin "2") (pinfunction "2_2") (pintype "bidirectional"))
      (node (ref "J13") (pin "2") (pinfunction "2_2") (pintype "bidirectional"))
      (node (ref "U1") (pin "15") (pinfunction "OC2B/ICP/PCINT30_15") (pintype "bidirectional"))
    )
    (net (code "19") (name "/D7") (class "Default")
      (node (ref "H2") (pin "18") (pinfunction "18_18") (pintype "bidirectional"))
      (node (ref "J11") (pin "2") (pinfunction "2_2") (pintype "bidirectional"))
      (node (ref "J12") (pin "2") (pinfunction "2_2") (pintype "bidirectional"))
      (node (ref "U1") (pin "16") (pinfunction "OC2A/PCINT31_16") (pintype "bidirectional"))
    )
    (net (code "20") (name "/D8") (class "Default")
      (node (ref "H2") (pin "4") (pinfunction "4_4") (pintype "bidirectional"))
      (node (ref "R8") (pin "1") (pinfunction "1_1") (pintype "passive"))
      (node (ref "U1") (pin "40") (pinfunction "T0/XCK0/PCINT8_40") (pintype "bidirectional"))
    )
    (net (code "21") (name "/D9") (class "Default")
      (node (ref "H2") (pin "17") (pinfunction "17_17") (pintype "bidirectional"))
      (node (ref "R9") (pin "1") (pinfunction "1_1") (pintype "passive"))
      (node (ref "U1") (pin "41") (pinfunction "T1/CLKO/PCINT9_41") (pintype "bidirectional"))
    )
    (net (code "22") (name "/D11") (class "Default")
      (node (ref "H2") (pin "16") (pinfunction "16_16") (pintype "bidirectional"))
      (node (ref "H6") (pin "2") (pinfunction "2_2") (pintype "bidirectional"))
      (node (ref "J10") (pin "2") (pinfunction "2_2") (pintype "bidirectional"))
      (node (ref "U1") (pin "43") (pinfunction "AIN1/OC0A/PCINT11_43") (pintype "bidirectional"))
    )
    (net (code "23") (name "/D21") (class "Default")
      (node (ref "SJ2") (pin "2") (pinfunction "2_2") (pintype "passive"))
      (node (ref "U1") (pin "24") (pinfunction "TDI/PCINT21_24") (pintype "bidirectional"))
    )
    (net (code "24") (name "/DTR") (class "Default")
      (node (ref "C4") (pin "1") (pinfunction "1_1") (pintype "passive"))
      (node (ref "H3") (pin "1") (pinfunction "1_1") (pintype "passive"))
    )
    (net (code "25") (name "/DTR2") (class "Default")
      (node (ref "C14") (pin "2") (pinfunction "2_2") (pintype "passive"))
      (node (ref "U3") (pin "16") (pinfunction "RTS_16") (pintype "bidirectional"))
    )
    (net (code "26") (name "/LIPO_V") (class "Default")
      (node (ref "C24") (pin "2") (pinfunction "2_2") (pintype "passive"))
      (node (ref "C25") (pin "2") (pinfunction "2_2") (pintype "passive"))
      (node (ref "J1") (pin "1") (pinfunction "1_1") (pintype "bidirectional"))
      (node (ref "J2") (pin "1") (pinfunction "1_1") (pintype "bidirectional"))
      (node (ref "SJ27") (pin "1") (pinfunction "1_1") (pintype "passive"))
      (node (ref "U9") (pin "2") (pinfunction "BAT_2") (pintype "input"))
      (node (ref "U9") (pin "3") (pinfunction "BAT_3") (pintype "input"))
    )
    (net (code "27") (name "/MISO") (class "Default")
      (node (ref "H4") (pin "P$1") (pinfunction "PIN1_P$1") (pintype "bidirectional"))
      (node (ref "J5") (pin "7") (pinfunction "DO_7") (pintype "bidirectional"))
      (node (ref "J7") (pin "6") (pinfunction "J_6") (pintype "passive"))
      (node (ref "U1") (pin "2") (pinfunction "MISO/OC3A/PCINT14_2") (pintype "bidirectional"))
      (node (ref "U12") (pin "2") (pinfunction "SO(D1)_2") (pintype "bidirectional"))
    )
    (net (code "28") (name "/MOSI") (class "Default")
      (node (ref "H4") (pin "P$4") (pinfunction "PIN4_P$4") (pintype "bidirectional"))
      (node (ref "J5") (pin "3") (pinfunction "DI_3") (pintype "bidirectional"))
      (node (ref "J7") (pin "2") (pinfunction "J_2") (pintype "passive"))
      (node (ref "U1") (pin "1") (pinfunction "MOSI/ICP3/PCINT13_1") (pintype "bidirectional"))
      (node (ref "U12") (pin "5") (pinfunction "SI(D0)_5") (pintype "bidirectional"))
    )
    (net (code "29") (name "/RI") (class "Default")
      (node (ref "H7-H8") (pin "20") (pinfunction "DIO0_20") (pintype "bidirectional"))
      (node (ref "SJ7") (pin "1") (pinfunction "1_1") (pintype "passive"))
    )
    (net (code "30") (name "/RXD0") (class "Default")
      (node (ref "H1") (pin "5") (pinfunction "5_5") (pintype "bidirectional"))
      (node (ref "H3") (pin "3") (pinfunction "3_3") (pintype "passive"))
      (node (ref "SJ9") (pin "1") (pinfunction "1_1") (pintype "passive"))
      (node (ref "U1") (pin "9") (pinfunction "T3/RXD0/PCINT24_9") (pintype "bidirectional"))
      (node (ref "U3") (pin "18") (pinfunction "TXD_18") (pintype "bidirectional"))
    )
    (net (code "31") (name "/RXD1") (class "Default")
      (node (ref "H1") (pin "6") (pinfunction "6_6") (pintype "bidirectional"))
      (node (ref "SJ9") (pin "3") (pinfunction "3_3") (pintype "passive"))
      (node (ref "U1") (pin "11") (pinfunction "RXD1/INT0/PCINT26_11") (pintype "bidirectional"))
    )
    (net (code "32") (name "/RXD_BEE") (class "Default")
      (node (ref "H7-H8") (pin "2") (pinfunction "DOUT_2") (pintype "output"))
      (node (ref "SJ9") (pin "2") (pinfunction "2_2") (pintype "passive"))
    )
    (net (code "33") (name "/SCK") (class "Default")
      (node (ref "H4") (pin "P$3") (pinfunction "PIN3_P$3") (pintype "bidirectional"))
      (node (ref "J5") (pin "5") (pinfunction "SCLK_5") (pintype "bidirectional"))
      (node (ref "J7") (pin "4") (pinfunction "J_4") (pintype "passive"))
      (node (ref "U1") (pin "3") (pinfunction "SCK/OC3B/PCINT15_3") (pintype "bidirectional"))
      (node (ref "U12") (pin "6") (pinfunction "SCK_6") (pintype "bidirectional"))
    )
    (net (code "34") (name "/SCL") (class "Default")
      (node (ref "H2") (pin "13") (pinfunction "13_13") (pintype "bidirectional"))
      (node (ref "J14") (pin "1") (pinfunction "1_1") (pintype "bidirectional"))
      (node (ref "J15") (pin "4") (pinfunction "4_4") (pintype "passive"))
      (node (ref "J16") (pin "4") (pinfunction "4_4") (pintype "passive"))
      (node (ref "R10") (pin "1") (pinfunction "1_1") (pintype "passive"))
      (node (ref "U1") (pin "19") (pinfunction "SCL/PCINT16_19") (pintype "bidirectional"))
      (node (ref "U13") (pin "2") (pinfunction "SCL_2") (pintype "input"))
      (node (ref "U14") (pin "6") (pinfunction "SCL_6") (pintype "bidirectional"))
      (node (ref "U2") (pin "8") (pinfunction "SCL_8") (pintype "bidirectional"))
      (node (ref "U7") (pin "10") (pinfunction "SCL_10") (pintype "bidirectional"))
    )
    (net (code "35") (name "/SDA") (class "Default")
      (node (ref "H2") (pin "8") (pinfunction "8_8") (pintype "bidirectional"))
      (node (ref "J14") (pin "2") (pinfunction "2_2") (pintype "bidirectional"))
      (node (ref "J15") (pin "3") (pinfunction "3_3") (pintype "passive"))
      (node (ref "J16") (pin "3") (pinfunction "3_3") (pintype "passive"))
      (node (ref "R7") (pin "2") (pinfunction "2_2") (pintype "passive"))
      (node (ref "U1") (pin "20") (pinfunction "SDA/PCINT17_20") (pintype "bidirectional"))
      (node (ref "U13") (pin "1") (pinfunction "SDA_1") (pintype "bidirectional"))
      (node (ref "U14") (pin "7") (pinfunction "SDA_7") (pintype "bidirectional"))
      (node (ref "U2") (pin "7") (pinfunction "SDA_7") (pintype "bidirectional"))
      (node (ref "U7") (pin "9") (pinfunction "SDA_9") (pintype "bidirectional"))
    )
    (net (code "36") (name "/TXD0") (class "Default")
      (node (ref "H1") (pin "16") (pinfunction "16_16") (pintype "bidirectional"))
      (node (ref "H3") (pin "2") (pinfunction "2_2") (pintype "passive"))
      (node (ref "SJ8") (pin "1") (pinfunction "1_1") (pintype "passive"))
      (node (ref "U1") (pin "10") (pinfunction "TXD0/PCINT25_10") (pintype "bidirectional"))
      (node (ref "U3") (pin "17") (pinfunction "RXD_17") (pintype "bidirectional"))
    )
    (net (code "37") (name "/TXD1") (class "Default")
      (node (ref "H1") (pin "15") (pinfunction "15_15") (pintype "bidirectional"))
      (node (ref "SJ8") (pin "3") (pinfunction "3_3") (pintype "passive"))
      (node (ref "U1") (pin "12") (pinfunction "TXD1/INT1/PCINT27_12") (pintype "bidirectional"))
    )
    (net (code "38") (name "/TXD_BEE") (class "Default")
      (node (ref "H7-H8") (pin "3") (pinfunction "DIN_3") (pintype "input"))
      (node (ref "SJ8") (pin "2") (pinfunction "2_2") (pintype "passive"))
    )
    (net (code "39") (name "/VIN") (class "Default")
      (node (ref "C8") (pin "2") (pinfunction "2_2") (pintype "passive"))
      (node (ref "D3") (pin "1") (pinfunction "1_1") (pintype "passive"))
      (node (ref "H10") (pin "2") (pinfunction "2_2") (pintype "passive"))
      (node (ref "Q1") (pin "2") (pinfunction "S_2") (pintype "passive"))
      (node (ref "S1") (pin "CH1A") (pinfunction "CH1A_CH1A") (pintype "bidirectional"))
      (node (ref "SJ27") (pin "3") (pinfunction "3_3") (pintype "passive"))
      (node (ref "U4") (pin "1") (pinfunction "VIN_1") (pintype "bidirectional"))
    )
    (net (code "40") (name "/X0") (class "Default")
      (node (ref "H2") (pin "6") (pinfunction "6_6") (pintype "bidirectional"))
      (node (ref "U14") (pin "1") (pinfunction "P0_1") (pintype "bidirectional"))
    )
    (net (code "41") (name "/X1") (class "Default")
      (node (ref "H2") (pin "15") (pinfunction "15_15") (pintype "bidirectional"))
      (node (ref "U14") (pin "2") (pinfunction "P1_2") (pintype "bidirectional"))
    )
    (net (code "42") (name "/X2") (class "Default")
      (node (ref "H2") (pin "7") (pinfunction "7_7") (pintype "bidirectional"))
      (node (ref "U14") (pin "3") (pinfunction "P2_3") (pintype "bidirectional"))
    )
    (net (code "43") (name "/X3") (class "Default")
      (node (ref "H2") (pin "14") (pinfunction "14_14") (pintype "bidirectional"))
      (node (ref "U14") (pin "5") (pinfunction "P3_5") (pintype "bidirectional"))
    )
    (net (code "44") (name "3.3V") (class "Default")
      (node (ref "C11") (pin "2") (pinfunction "2_2") (pintype "passive"))
      (node (ref "C12") (pin "2") (pinfunction "2_2") (pintype "passive"))
      (node (ref "C15") (pin "2") (pinfunction "2_2") (pintype "passive"))
      (node (ref "C17") (pin "1") (pinfunction "1_1") (pintype "passive"))
      (node (ref "C29") (pin "2") (pinfunction "2_2") (pintype "passive"))
      (node (ref "C30") (pin "2") (pinfunction "2_2") (pintype "passive"))
      (node (ref "C31") (pin "2") (pinfunction "2_2") (pintype "passive"))
      (node (ref "C32") (pin "2") (pinfunction "2_2") (pintype "passive"))
      (node (ref "C36") (pin "2") (pinfunction "2_2") (pintype "passive"))
      (node (ref "C37") (pin "2") (pinfunction "2_2") (pintype "passive"))
      (node (ref "H1") (pin "1") (pinfunction "1_1") (pintype "bidirectional"))
      (node (ref "H2") (pin "1") (pinfunction "1_1") (pintype "bidirectional"))
      (node (ref "H4") (pin "P$2") (pinfunction "PIN2_P$2") (pintype "bidirectional"))
      (node (ref "J14") (pin "3") (pinfunction "3_3") (pintype "bidirectional"))
      (node (ref "J15") (pin "2") (pinfunction "2_2") (pintype "power_in"))
      (node (ref "J16") (pin "2") (pinfunction "2_2") (pintype "power_in"))
      (node (ref "J5") (pin "4") (pinfunction "VDD_4") (pintype "bidirectional"))
      (node (ref "J7") (pin "3") (pinfunction "J_3") (pintype "passive"))
      (node (ref "JP5") (pin "4") (pinfunction "4_4") (pintype "bidirectional"))
      (node (ref "R10") (pin "2") (pinfunction "2_2") (pintype "passive"))
      (node (ref "R17") (pin "1") (pinfunction "1_1") (pintype "passive"))
      (node (ref "R20") (pin "2") (pinfunction "2_2") (pintype "passive"))
      (node (ref "R3") (pin "2") (pinfunction "2_2") (pintype "passive"))
      (node (ref "R34") (pin "1") (pinfunction "1_1") (pintype "passive"))
      (node (ref "R44") (pin "1") (pinfunction "1_1") (pintype "passive"))
      (node (ref "R7") (pin "1") (pinfunction "1_1") (pintype "passive"))
      (node (ref "S2") (pin "3") (pinfunction "COM_1_3") (pintype "bidirectional"))
      (node (ref "S2") (pin "4") (pinfunction "COM_2_4") (pintype "bidirectional"))
      (node (ref "S4") (pin "1A") (pinfunction "COM1_1A") (pintype "passive"))
      (node (ref "SJ18") (pin "1") (pinfunction "1_1") (pintype "passive"))
      (node (ref "SJ21") (pin "2") (pinfunction "2_2") (pintype "passive"))
      (node (ref "SJ22") (pin "1") (pinfunction "1_1") (pintype "passive"))
      (node (ref "SJ23") (pin "1") (pinfunction "1_1") (pintype "passive"))
      (node (ref "U1") (pin "17") (pinfunction "VCC_2_17") (pintype "bidirectional"))
      (node (ref "U1") (pin "27") (pinfunction "AVCC_27") (pintype "bidirectional"))
      (node (ref "U1") (pin "38") (pinfunction "VCC_3_38") (pintype "bidirectional"))
      (node (ref "U1") (pin "5") (pinfunction "VCC_1_5") (pintype "bidirectional"))
      (node (ref "U12") (pin "3") (pinfunction "~{WP}(D2)_3") (pintype "bidirectional"))
      (node (ref "U12") (pin "7") (pinfunction "~{HOLD}(D3)_7") (pintype "bidirectional"))
      (node (ref "U12") (pin "8") (pinfunction "VCC_8") (pintype "bidirectional"))
      (node (ref "U14") (pin "8") (pinfunction "VCC_8") (pintype "bidirectional"))
      (node (ref "U2") (pin "2") (pinfunction "VCC_2") (pintype "bidirectional"))
      (node (ref "U4") (pin "5") (pinfunction "VOUT_5") (pintype "bidirectional"))
      (node (ref "U7") (pin "8") (pinfunction "VDD_8") (pintype "bidirectional"))
    )
    (net (code "45") (name "3.3V_SW") (class "Default")
      (node (ref "C16") (pin "2") (pinfunction "2_2") (pintype "passive"))
      (node (ref "C34") (pin "2") (pinfunction "2_2") (pintype "passive"))
      (node (ref "H1") (pin "10") (pinfunction "10_10") (pintype "bidirectional"))
      (node (ref "H2") (pin "10") (pinfunction "10_10") (pintype "bidirectional"))
      (node (ref "JP1") (pin "4") (pinfunction "4_4") (pintype "bidirectional"))
      (node (ref "JP2") (pin "4") (pinfunction "4_4") (pintype "bidirectional"))
      (node (ref "JP3") (pin "4") (pinfunction "4_4") (pintype "bidirectional"))
      (node (ref "JP4") (pin "4") (pinfunction "4_4") (pintype "bidirectional"))
      (node (ref "JP5") (pin "2") (pinfunction "2_2") (pintype "bidirectional"))
      (node (ref "L2") (pin "1") (pinfunction "1_1") (pintype "bidirectional"))
      (node (ref "SJ3") (pin "1") (pinfunction "1_1") (pintype "passive"))
      (node (ref "U5") (pin "5") (pinfunction "VOUT_5") (pintype "bidirectional"))
      (node (ref "U8") (pin "5") (pinfunction "IN_5") (pintype "bidirectional"))
    )
    (net (code "46") (name "5V_CP_SW") (class "Default")
      (node (ref "C10") (pin "2") (pinfunction "2_2") (pintype "passive"))
      (node (ref "C5") (pin "2") (pinfunction "2_2") (pintype "passive"))
      (node (ref "R24") (pin "2") (pinfunction "2_2") (pintype "passive"))
      (node (ref "S1") (pin "COM2") (pinfunction "COM2_COM2") (pintype "bidirectional"))
      (node (ref "U3") (pin "7") (pinfunction "VREGIN_7") (pintype "bidirectional"))
    )
    (net (code "47") (name "5V_SW") (class "Default")
      (node (ref "C18") (pin "1") (pinfunction "1_1") (pintype "passive"))
      (node (ref "C39") (pin "1") (pinfunction "1_1") (pintype "passive"))
      (node (ref "C7") (pin "1") (pinfunction "1_1") (pintype "passive"))
      (node (ref "H1") (pin "11") (pinfunction "11_11") (pintype "bidirectional"))
      (node (ref "H2") (pin "11") (pinfunction "11_11") (pintype "bidirectional"))
      (node (ref "JP1") (pin "2") (pinfunction "2_2") (pintype "bidirectional"))
      (node (ref "JP2") (pin "2") (pinfunction "2_2") (pintype "bidirectional"))
      (node (ref "JP3") (pin "2") (pinfunction "2_2") (pintype "bidirectional"))
      (node (ref "JP4") (pin "2") (pinfunction "2_2") (pintype "bidirectional"))
      (node (ref "JP5") (pin "6") (pinfunction "6_6") (pintype "bidirectional"))
      (node (ref "L1") (pin "1") (pinfunction "1_1") (pintype "bidirectional"))
      (node (ref "U10") (pin "5") (pinfunction "MODE_5") (pintype "bidirectional"))
      (node (ref "U10") (pin "6") (pinfunction "VIN_6") (pintype "bidirectional"))
      (node (ref "U8") (pin "1") (pinfunction "OUT_1") (pintype "bidirectional"))
    )
    (net (code "48") (name "12V_SW") (class "Default")
      (node (ref "C13") (pin "2") (pinfunction "2_2") (pintype "passive"))
      (node (ref "C20") (pin "2") (pinfunction "2_2") (pintype "passive"))
      (node (ref "C35") (pin "2") (pinfunction "2_2") (pintype "passive"))
      (node (ref "C38") (pin "2") (pinfunction "2_2") (pintype "passive"))
      (node (ref "D7") (pin "1") (pinfunction "1_1") (pintype "passive"))
      (node (ref "H1") (pin "9") (pinfunction "9_9") (pintype "bidirectional"))
      (node (ref "H2") (pin "9") (pinfunction "9_9") (pintype "bidirectional"))
      (node (ref "JP1") (pin "6") (pinfunction "6_6") (pintype "bidirectional"))
      (node (ref "JP2") (pin "6") (pinfunction "6_6") (pintype "bidirectional"))
      (node (ref "JP3") (pin "6") (pinfunction "6_6") (pintype "bidirectional"))
      (node (ref "JP4") (pin "6") (pinfunction "6_6") (pintype "bidirectional"))
      (node (ref "R19") (pin "1") (pinfunction "1_1") (pintype "passive"))
      (node (ref "SJ25") (pin "2") (pinfunction "2_2") (pintype "passive"))
    )
    (net (code "49") (name "A3") (class "Default")
      (node (ref "H1") (pin "18") (pinfunction "18_18") (pintype "bidirectional"))
      (node (ref "SJ7") (pin "2") (pinfunction "2_2") (pintype "passive"))
      (node (ref "U1") (pin "34") (pinfunction "ADC3/PCINT3_34") (pintype "bidirectional"))
    )
    (net (code "50") (name "A4") (class "Default")
      (node (ref "H1") (pin "4") (pinfunction "4_4") (pintype "bidirectional"))
      (node (ref "SJ24") (pin "2") (pinfunction "2_2") (pintype "passive"))
      (node (ref "U1") (pin "33") (pinfunction "ADC4/PCINT4_33") (pintype "bidirectional"))
    )
    (net (code "51") (name "A5") (class "Default")
      (node (ref "SJ20") (pin "2") (pinfunction "2_2") (pintype "passive"))
      (node (ref "U1") (pin "32") (pinfunction "ADC5/PCINT5_32") (pintype "bidirectional"))
    )
    (net (code "52") (name "A6") (class "Default")
      (node (ref "C1") (pin "2") (pinfunction "2_2") (pintype "passive"))
      (node (ref "R1") (pin "1") (pinfunction "1_1") (pintype "passive"))
      (node (ref "R2") (pin "2") (pinfunction "2_2") (pintype "passive"))
      (node (ref "U1") (pin "31") (pinfunction "ADC6/PCINT6_31") (pintype "bidirectional"))
    )
    (net (code "53") (name "A7") (class "Default")
      (node (ref "H1") (pin "17") (pinfunction "17_17") (pintype "bidirectional"))
      (node (ref "SJ1") (pin "3") (pinfunction "3_3") (pintype "passive"))
      (node (ref "U1") (pin "30") (pinfunction "ADC7/PCINT7_30") (pintype "bidirectional"))
    )
    (net (code "54") (name "BEE_VCC") (class "Default")
      (node (ref "C40") (pin "+") (pinfunction "+_+") (pintype "passive"))
      (node (ref "C6") (pin "2") (pinfunction "2_2") (pintype "passive"))
      (node (ref "H7-H8") (pin "1") (pinfunction "VDD_1") (pintype "power_in"))
      (node (ref "SJ16") (pin "1") (pinfunction "1_1") (pintype "passive"))
      (node (ref "U6") (pin "5") (pinfunction "VOUT_5") (pintype "bidirectional"))
    )
    (net (code "55") (name "D10") (class "Default")
      (node (ref "H2") (pin "5") (pinfunction "5_5") (pintype "bidirectional"))
      (node (ref "H6") (pin "1") (pinfunction "1_1") (pintype "bidirectional"))
      (node (ref "J10") (pin "1") (pinfunction "1_1") (pintype "bidirectional"))
      (node (ref "SJ1") (pin "1") (pinfunction "1_1") (pintype "passive"))
      (node (ref "SJ12") (pin "1") (pinfunction "1_1") (pintype "passive"))
      (node (ref "U1") (pin "42") (pinfunction "AIN0/INT2/PCINT10_42") (pintype "bidirectional"))
    )
    (net (code "56") (name "D12") (class "Default")
      (node (ref "J5") (pin "2") (pinfunction "CS_2") (pintype "bidirectional"))
      (node (ref "J7") (pin "1") (pinfunction "J_1") (pintype "passive"))
      (node (ref "R34") (pin "2") (pinfunction "2_2") (pintype "passive"))
      (node (ref "U1") (pin "44") (pinfunction "~{SS}/OC0B/PCINT12_44") (pintype "bidirectional"))
    )
    (net (code "57") (name "D18") (class "Default")
      (node (ref "R33") (pin "2") (pinfunction "2_2") (pintype "passive"))
      (node (ref "SJ18") (pin "3") (pinfunction "3_3") (pintype "passive"))
      (node (ref "U1") (pin "21") (pinfunction "TCK/PCINT18_21") (pintype "bidirectional"))
    )
    (net (code "58") (name "D19") (class "Default")
      (node (ref "SJ19") (pin "2") (pinfunction "2_2") (pintype "passive"))
      (node (ref "U1") (pin "22") (pinfunction "TMS/PCINT19_22") (pintype "bidirectional"))
    )
    (net (code "59") (name "D20") (class "Default")
      (node (ref "R44") (pin "2") (pinfunction "2_2") (pintype "passive"))
      (node (ref "U1") (pin "23") (pinfunction "TDO/PCINT20_23") (pintype "bidirectional"))
      (node (ref "U12") (pin "1") (pinfunction "~{CS}_1") (pintype "bidirectional"))
    )
    (net (code "60") (name "D22") (class "Default")
      (node (ref "R14") (pin "2") (pinfunction "2_2") (pintype "passive"))
      (node (ref "U1") (pin "25") (pinfunction "TOSC1/PCINT22_25") (pintype "bidirectional"))
      (node (ref "U10") (pin "7") (pinfunction "EN_7") (pintype "bidirectional"))
      (node (ref "U5") (pin "3") (pinfunction "CE_3") (pintype "bidirectional"))
      (node (ref "U8") (pin "6") (pinfunction "EN_6") (pintype "bidirectional"))
    )
    (net (code "61") (name "D23") (class "Default")
      (node (ref "H7-H8") (pin "9") (pinfunction "DTR_9") (pintype "bidirectional"))
      (node (ref "U1") (pin "26") (pinfunction "TOSC2/PCINT23_26") (pintype "bidirectional"))
    )
    (net (code "62") (name "GND") (class "Default")
      (node (ref "BAT1") (pin "-") (pinfunction "V-_-") (pintype "bidirectional"))
      (node (ref "C1") (pin "1") (pinfunction "1_1") (pintype "passive"))
      (node (ref "C10") (pin "1") (pinfunction "1_1") (pintype "passive"))
      (node (ref "C11") (pin "1") (pinfunction "1_1") (pintype "passive"))
      (node (ref "C12") (pin "1") (pinfunction "1_1") (pintype "passive"))
      (node (ref "C13") (pin "1") (pinfunction "1_1") (pintype "passive"))
      (node (ref "C15") (pin "1") (pinfunction "1_1") (pintype "passive"))
      (node (ref "C16") (pin "1") (pinfunction "1_1") (pintype "passive"))
      (node (ref "C17") (pin "2") (pinfunction "2_2") (pintype "passive"))
      (node (ref "C18") (pin "2") (pinfunction "2_2") (pintype "passive"))
      (node (ref "C19") (pin "1") (pinfunction "1_1") (pintype "passive"))
      (node (ref "C2") (pin "1") (pinfunction "1_1") (pintype "passive"))
      (node (ref "C20") (pin "1") (pinfunction "1_1") (pintype "passive"))
      (node (ref "C21") (pin "1") (pinfunction "1_1") (pintype "passive"))
      (node (ref "C22") (pin "1") (pinfunction "1_1") (pintype "passive"))
      (node (ref "C23") (pin "1") (pinfunction "1_1") (pintype "passive"))
      (node (ref "C24") (pin "1") (pinfunction "1_1") (pintype "passive"))
      (node (ref "C25") (pin "1") (pinfunction "1_1") (pintype "passive"))
      (node (ref "C26") (pin "1") (pinfunction "1_1") (pintype "passive"))
      (node (ref "C27") (pin "1") (pinfunction "1_1") (pintype "passive"))
      (node (ref "C28") (pin "1") (pinfunction "1_1") (pintype "passive"))
      (node (ref "C29") (pin "1") (pinfunction "1_1") (pintype "passive"))
      (node (ref "C3") (pin "1") (pinfunction "1_1") (pintype "passive"))
      (node (ref "C30") (pin "1") (pinfunction "1_1") (pintype "passive"))
      (node (ref "C31") (pin "1") (pinfunction "1_1") (pintype "passive"))
      (node (ref "C32") (pin "1") (pinfunction "1_1") (pintype "passive"))
      (node (ref "C33") (pin "1") (pinfunction "1_1") (pintype "passive"))
      (node (ref "C34") (pin "1") (pinfunction "1_1") (pintype "passive"))
      (node (ref "C35") (pin "1") (pinfunction "1_1") (pintype "passive"))
      (node (ref "C36") (pin "1") (pinfunction "1_1") (pintype "passive"))
      (node (ref "C37") (pin "1") (pinfunction "1_1") (pintype "passive"))
      (node (ref "C38") (pin "1") (pinfunction "1_1") (pintype "passive"))
      (node (ref "C39") (pin "2") (pinfunction "2_2") (pintype "passive"))
      (node (ref "C40") (pin "-") (pinfunction "-_-") (pintype "passive"))
      (node (ref "C5") (pin "1") (pinfunction "1_1") (pintype "passive"))
      (node (ref "C6") (pin "1") (pinfunction "1_1") (pintype "passive"))
      (node (ref "C7") (pin "2") (pinfunction "2_2") (pintype "passive"))
      (node (ref "C8") (pin "1") (pinfunction "1_1") (pintype "passive"))
      (node (ref "C9") (pin "1") (pinfunction "1_1") (pintype "passive"))
      (node (ref "D6") (pin "1") (pinfunction "1_1") (pintype "passive"))
      (node (ref "H1") (pin "20") (pinfunction "20_20") (pintype "bidirectional"))
      (node (ref "H2") (pin "20") (pinfunction "20_20") (pintype "bidirectional"))
      (node (ref "H3") (pin "5") (pinfunction "5_5") (pintype "passive"))
      (node (ref "H3") (pin "6") (pinfunction "6_6") (pintype "passive"))
      (node (ref "H4") (pin "P$6") (pinfunction "PIN6_P$6") (pintype "bidirectional"))
      (node (ref "H5") (pin "4") (pinfunction "4_4") (pintype "bidirectional"))
      (node (ref "H6") (pin "4") (pinfunction "4_4") (pintype "bidirectional"))
      (node (ref "H7-H8") (pin "10") (pinfunction "GND_10") (pintype "power_in"))
      (node (ref "J1") (pin "2") (pinfunction "2_2") (pintype "bidirectional"))
      (node (ref "J10") (pin "4") (pinfunction "4_4") (pintype "bidirectional"))
      (node (ref "J11") (pin "4") (pinfunction "4_4") (pintype "bidirectional"))
      (node (ref "J12") (pin "4") (pinfunction "4_4") (pintype "bidirectional"))
      (node (ref "J13") (pin "4") (pinfunction "4_4") (pintype "bidirectional"))
      (node (ref "J14") (pin "4") (pinfunction "4_4") (pintype "bidirectional"))
      (node (ref "J15") (pin "1") (pinfunction "1_1") (pintype "power_in"))
      (node (ref "J16") (pin "1") (pinfunction "1_1") (pintype "power_in"))
      (node (ref "J2") (pin "2") (pinfunction "2_2") (pintype "bidirectional"))
      (node (ref "J3") (pin "2") (pinfunction "2_2") (pintype "bidirectional"))
      (node (ref "J4") (pin "2") (pinfunction "2_2") (pintype "bidirectional"))
      (node (ref "J5") (pin "6") (pinfunction "VSS_6") (pintype "bidirectional"))
      (node (ref "J5") (pin "G1") (pinfunction "G1_G1") (pintype "bidirectional"))
      (node (ref "J5") (pin "G2") (pinfunction "G2_G2") (pintype "bidirectional"))
      (node (ref "J5") (pin "G3") (pinfunction "G3_G3") (pintype "bidirectional"))
      (node (ref "J5") (pin "G4") (pinfunction "G4_G4") (pintype "bidirectional"))
      (node (ref "J6") (pin "A1/B12") (pinfunction "GND_A1/B12") (pintype "power_in"))
      (node (ref "J6") (pin "B1/A12") (pinfunction "GND_B1/A12") (pintype "power_in"))
      (node (ref "J6") (pin "G1") (pinfunction "GND_G1") (pintype "power_in"))
      (node (ref "J6") (pin "G2") (pinfunction "GND_G2") (pintype "power_in"))
      (node (ref "J6") (pin "G3") (pinfunction "GND_G3") (pintype "power_in"))
      (node (ref "J6") (pin "G4") (pinfunction "GND_G4") (pintype "power_in"))
      (node (ref "J7") (pin "5") (pinfunction "J_5") (pintype "passive"))
      (node (ref "J8") (pin "4") (pinfunction "4_4") (pintype "bidirectional"))
      (node (ref "J9") (pin "4") (pinfunction "4_4") (pintype "bidirectional"))
      (node (ref "LED10") (pin "C") (pinfunction "C_C") (pintype "passive"))
      (node (ref "LED2") (pin "C") (pinfunction "C_C") (pintype "passive"))
      (node (ref "LED3") (pin "C") (pinfunction "C_C") (pintype "passive"))
      (node (ref "LED7") (pin "C") (pinfunction "C_C") (pintype "passive"))
      (node (ref "LED8") (pin "C") (pinfunction "C_C") (pintype "passive"))
      (node (ref "LED9") (pin "C") (pinfunction "C_C") (pintype "passive"))
      (node (ref "R13") (pin "1") (pinfunction "1_1") (pintype "passive"))
      (node (ref "R14") (pin "1") (pinfunction "1_1") (pintype "passive"))
      (node (ref "R15") (pin "2") (pinfunction "2_2") (pintype "passive"))
      (node (ref "R16") (pin "2") (pinfunction "2_2") (pintype "passive"))
      (node (ref "R2") (pin "1") (pinfunction "1_1") (pintype "passive"))
      (node (ref "R25") (pin "1") (pinfunction "1_1") (pintype "passive"))
      (node (ref "R26") (pin "1") (pinfunction "1_1") (pintype "passive"))
      (node (ref "R27") (pin "1") (pinfunction "1_1") (pintype "passive"))
      (node (ref "R28") (pin "2") (pinfunction "2_2") (pintype "passive"))
      (node (ref "R30") (pin "2") (pinfunction "2_2") (pintype "passive"))
      (node (ref "R33") (pin "1") (pinfunction "1_1") (pintype "passive"))
      (node (ref "R35") (pin "1") (pinfunction "1_1") (pintype "passive"))
      (node (ref "R40") (pin "1") (pinfunction "1_1") (pintype "passive"))
      (node (ref "R41") (pin "1") (pinfunction "1_1") (pintype "passive"))
      (node (ref "R43") (pin "2") (pinfunction "2_2") (pintype "passive"))
      (node (ref "R6") (pin "1") (pinfunction "1_1") (pintype "passive"))
      (node (ref "S3") (pin "1") (pinfunction "1_1") (pintype "passive"))
      (node (ref "S3") (pin "2") (pinfunction "2_2") (pintype "passive"))
      (node (ref "SJ14") (pin "2") (pinfunction "2_2") (pintype "passive"))
      (node (ref "SJ15") (pin "1") (pinfunction "1_1") (pintype "passive"))
      (node (ref "U1") (pin "18") (pinfunction "GND_2_18") (pintype "bidirectional"))
      (node (ref "U1") (pin "28") (pinfunction "GND_3_28") (pintype "bidirectional"))
      (node (ref "U1") (pin "39") (pinfunction "GND_4_39") (pintype "bidirectional"))
      (node (ref "U1") (pin "6") (pinfunction "GND_1_6") (pintype "bidirectional"))
      (node (ref "U10") (pin "1") (pinfunction "PGND1_1") (pintype "bidirectional"))
      (node (ref "U10") (pin "10") (pinfunction "PGND3_10") (pintype "bidirectional"))
      (node (ref "U10") (pin "11") (pinfunction "EPAD_11") (pintype "bidirectional"))
      (node (ref "U10") (pin "2") (pinfunction "PGND2_2") (pintype "bidirectional"))
      (node (ref "U10") (pin "3") (pinfunction "SGND_3") (pintype "bidirectional"))
      (node (ref "U12") (pin "4") (pinfunction "GND_4") (pintype "bidirectional"))
      (node (ref "U13") (pin "4") (pinfunction "VSS_4") (pintype "passive"))
      (node (ref "U14") (pin "4") (pinfunction "GND_4") (pintype "bidirectional"))
      (node (ref "U2") (pin "5") (pinfunction "GND_5") (pintype "bidirectional"))
      (node (ref "U3") (pin "12") (pinfunction "GND_2_12") (pintype "bidirectional"))
      (node (ref "U3") (pin "21") (pinfunction "EP_GND_21") (pintype "bidirectional"))
      (node (ref "U3") (pin "3") (pinfunction "GND_1_3") (pintype "bidirectional"))
      (node (ref "U4") (pin "2") (pinfunction "VSS_2") (pintype "bidirectional"))
      (node (ref "U5") (pin "2") (pinfunction "VSS_2") (pintype "bidirectional"))
      (node (ref "U6") (pin "2") (pinfunction "VSS_2") (pintype "bidirectional"))
      (node (ref "U7") (pin "3") (pinfunction "GND_3") (pintype "bidirectional"))
      (node (ref "U8") (pin "3") (pinfunction "GND_3") (pintype "bidirectional"))
      (node (ref "U8") (pin "4") (pinfunction "SEL_4") (pintype "bidirectional"))
      (node (ref "U9") (pin "14") (pinfunction "TMR_14") (pintype "input"))
      (node (ref "U9") (pin "4") (pinfunction "~{CE}_4") (pintype "input"))
      (node (ref "U9") (pin "6") (pinfunction "EN1_6") (pintype "input"))
      (node (ref "U9") (pin "8") (pinfunction "VSS_8") (pintype "power_in"))
      (node (ref "U9") (pin "THERMAL") (pinfunction "VSS_THERMAL") (pintype "power_in"))
      (node (ref "Y1") (pin "2") (pinfunction "2_2") (pintype "passive"))
    )
    (net (code "63") (name "Net-(H5-Pad3)") (class "Default")
      (node (ref "H5") (pin "3") (pinfunction "3_3") (pintype "bidirectional"))
      (node (ref "J13") (pin "3") (pinfunction "3_3") (pintype "bidirectional"))
      (node (ref "JP5") (pin "5") (pinfunction "5_5") (pintype "bidirectional"))
    )
    (net (code "64") (name "Net-(H6-Pad3)") (class "Default")
      (node (ref "H6") (pin "3") (pinfunction "3_3") (pintype "bidirectional"))
      (node (ref "J10") (pin "3") (pinfunction "3_3") (pintype "bidirectional"))
      (node (ref "JP2") (pin "5") (pinfunction "5_5") (pintype "bidirectional"))
    )
    (net (code "65") (name "Net-(H7-H8-BEE_CTS)") (class "Default")
      (node (ref "H7-H8") (pin "12") (pinfunction "BEE_CTS_12") (pintype "output"))
      (node (ref "SJ19") (pin "3") (pinfunction "3_3") (pintype "passive"))
    )
    (net (code "66") (name "Net-(H7-H8-DIO5)") (class "Default")
      (node (ref "H7-H8") (pin "15") (pinfunction "DIO5_15") (pintype "bidirectional"))
      (node (ref "SJ17") (pin "2") (pinfunction "2_2") (pintype "passive"))
    )
    (net (code "67") (name "Net-(H7-H8-DIO9)") (class "Default")
      (node (ref "H7-H8") (pin "13") (pinfunction "DIO9_13") (pintype "bidirectional"))
      (node (ref "SJ19") (pin "1") (pinfunction "1_1") (pintype "passive"))
    )
    (net (code "68") (name "Net-(H7-H8-RESET)") (class "Default")
      (node (ref "C3") (pin "2") (pinfunction "2_2") (pintype "passive"))
      (node (ref "H7-H8") (pin "5") (pinfunction "RESET_5") (pintype "input"))
      (node (ref "R42") (pin "1") (pinfunction "1_1") (pintype "passive"))
      (node (ref "SJ20") (pin "3") (pinfunction "3_3") (pintype "passive"))
    )
    (net (code "69") (name "Net-(J6-CC1)") (class "Default")
      (node (ref "J6") (pin "A5") (pinfunction "CC1_A5") (pintype "bidirectional"))
      (node (ref "R28") (pin "1") (pinfunction "1_1") (pintype "passive"))
    )
    (net (code "70") (name "Net-(J6-CC2)") (class "Default")
      (node (ref "J6") (pin "B5") (pinfunction "CC2_B5") (pintype "bidirectional"))
      (node (ref "R30") (pin "1") (pinfunction "1_1") (pintype "passive"))
    )
    (net (code "71") (name "Net-(J8-Pad3)") (class "Default")
      (node (ref "J8") (pin "3") (pinfunction "3_3") (pintype "bidirectional"))
      (node (ref "J9") (pin "3") (pinfunction "3_3") (pintype "bidirectional"))
      (node (ref "JP1") (pin "5") (pinfunction "5_5") (pintype "bidirectional"))
    )
    (net (code "72") (name "Net-(J11-Pad3)") (class "Default")
      (node (ref "J11") (pin "3") (pinfunction "3_3") (pintype "bidirectional"))
      (node (ref "JP4") (pin "5") (pinfunction "5_5") (pintype "bidirectional"))
    )
    (net (code "73") (name "Net-(J12-Pad3)") (class "Default")
      (node (ref "J12") (pin "3") (pinfunction "3_3") (pintype "bidirectional"))
      (node (ref "JP3") (pin "5") (pinfunction "5_5") (pintype "bidirectional"))
    )
    (net (code "74") (name "Net-(LED1-PadC)") (class "Default")
      (node (ref "LED1") (pin "C") (pinfunction "C_C") (pintype "passive"))
      (node (ref "R27") (pin "2") (pinfunction "2_2") (pintype "passive"))
    )
    (net (code "75") (name "Net-(LED2-PadA)") (class "Default")
      (node (ref "LED2") (pin "A") (pinfunction "A_A") (pintype "passive"))
      (node (ref "R29") (pin "2") (pinfunction "2_2") (pintype "passive"))
    )
    (net (code "76") (name "Net-(LED3-PadA)") (class "Default")
      (node (ref "LED3") (pin "A") (pinfunction "A_A") (pintype "passive"))
      (node (ref "R12") (pin "1") (pinfunction "1_1") (pintype "passive"))
    )
    (net (code "77") (name "Net-(LED4-PadA)") (class "Default")
      (node (ref "LED4") (pin "A") (pinfunction "A_A") (pintype "passive"))
      (node (ref "R4") (pin "2") (pinfunction "2_2") (pintype "passive"))
    )
    (net (code "78") (name "Net-(LED5-PadA)") (class "Default")
      (node (ref "LED5") (pin "A") (pinfunction "A_A") (pintype "passive"))
      (node (ref "R22") (pin "2") (pinfunction "2_2") (pintype "passive"))
    )
    (net (code "79") (name "Net-(LED6-PadA)") (class "Default")
      (node (ref "LED6") (pin "A") (pinfunction "A_A") (pintype "passive"))
      (node (ref "R23") (pin "2") (pinfunction "2_2") (pintype "passive"))
    )
    (net (code "80") (name "Net-(LED7-PadA)") (class "Default")
      (node (ref "LED7") (pin "A") (pinfunction "A_A") (pintype "passive"))
      (node (ref "R32") (pin "1") (pinfunction "1_1") (pintype "passive"))
    )
    (net (code "81") (name "Net-(LED8-PadA)") (class "Default")
      (node (ref "LED8") (pin "A") (pinfunction "A_A") (pintype "passive"))
      (node (ref "R8") (pin "2") (pinfunction "2_2") (pintype "passive"))
    )
    (net (code "82") (name "Net-(LED9-PadA)") (class "Default")
      (node (ref "LED9") (pin "A") (pinfunction "A_A") (pintype "passive"))
      (node (ref "R9") (pin "2") (pinfunction "2_2") (pintype "passive"))
    )
    (net (code "83") (name "Net-(LED10-PadA)") (class "Default")
      (node (ref "LED10") (pin "A") (pinfunction "A_A") (pintype "passive"))
      (node (ref "R36") (pin "2") (pinfunction "2_2") (pintype "passive"))
    )
    (net (code "84") (name "Net-(Q2-S)") (class "Default")
      (node (ref "C9") (pin "2") (pinfunction "2_2") (pintype "passive"))
      (node (ref "D4") (pin "1") (pinfunction "1_1") (pintype "passive"))
      (node (ref "Q2") (pin "2") (pinfunction "S_2") (pintype "passive"))
      (node (ref "U5") (pin "1") (pinfunction "VIN_1") (pintype "bidirectional"))
    )
    (net (code "85") (name "Net-(Q3-S)") (class "Default")
      (node (ref "C21") (pin "2") (pinfunction "2_2") (pintype "passive"))
      (node (ref "D5") (pin "1") (pinfunction "1_1") (pintype "passive"))
      (node (ref "Q3") (pin "2") (pinfunction "S_2") (pintype "passive"))
      (node (ref "U6") (pin "1") (pinfunction "VIN_1") (pintype "bidirectional"))
    )
    (net (code "86") (name "Net-(Q4-C)") (class "Default")
      (node (ref "Q4") (pin "1") (pinfunction "C_1") (pintype "passive"))
      (node (ref "SJ23") (pin "2") (pinfunction "2_2") (pintype "passive"))
    )
    (net (code "87") (name "Net-(Q4-E)") (class "Default")
      (node (ref "Q4") (pin "2") (pinfunction "E_2") (pintype "passive"))
      (node (ref "R43") (pin "1") (pinfunction "1_1") (pintype "passive"))
      (node (ref "SJ24") (pin "1") (pinfunction "1_1") (pintype "passive"))
    )
    (net (code "88") (name "Net-(R1-Pad2)") (class "Default")
      (node (ref "R1") (pin "2") (pinfunction "2_2") (pintype "passive"))
      (node (ref "SJ27") (pin "2") (pinfunction "2_2") (pintype "passive"))
    )
    (net (code "89") (name "Net-(R4-Pad1)") (class "Default")
      (node (ref "R4") (pin "1") (pinfunction "1_1") (pintype "passive"))
      (node (ref "SJ4") (pin "2") (pinfunction "2_2") (pintype "passive"))
    )
    (net (code "90") (name "Net-(R5-Pad1)") (class "Default")
      (node (ref "R5") (pin "1") (pinfunction "1_1") (pintype "passive"))
      (node (ref "SJ14") (pin "1") (pinfunction "1_1") (pintype "passive"))
    )
    (net (code "91") (name "Net-(R11-Pad2)") (class "Default")
      (node (ref "R11") (pin "2") (pinfunction "2_2") (pintype "passive"))
      (node (ref "SJ2") (pin "1") (pinfunction "1_1") (pintype "passive"))
    )
    (net (code "92") (name "Net-(R12-Pad2)") (class "Default")
      (node (ref "R12") (pin "2") (pinfunction "2_2") (pintype "passive"))
      (node (ref "SJ3") (pin "2") (pinfunction "2_2") (pintype "passive"))
    )
    (net (code "93") (name "Net-(R20-Pad1)") (class "Default")
      (node (ref "R20") (pin "1") (pinfunction "1_1") (pintype "passive"))
      (node (ref "SJ12") (pin "2") (pinfunction "2_2") (pintype "passive"))
    )
    (net (code "94") (name "Net-(R31-Pad1)") (class "Default")
      (node (ref "R31") (pin "1") (pinfunction "1_1") (pintype "passive"))
      (node (ref "SJ25") (pin "1") (pinfunction "1_1") (pintype "passive"))
    )
    (net (code "95") (name "Net-(R32-Pad2)") (class "Default")
      (node (ref "R32") (pin "2") (pinfunction "2_2") (pintype "passive"))
      (node (ref "SJ16") (pin "2") (pinfunction "2_2") (pintype "passive"))
    )
    (net (code "96") (name "Net-(R36-Pad1)") (class "Default")
      (node (ref "R36") (pin "1") (pinfunction "1_1") (pintype "passive"))
      (node (ref "SJ17") (pin "1") (pinfunction "1_1") (pintype "passive"))
    )
    (net (code "97") (name "Net-(R39-Pad1)") (class "Default")
      (node (ref "R39") (pin "1") (pinfunction "1_1") (pintype "passive"))
      (node (ref "SJ15") (pin "2") (pinfunction "2_2") (pintype "passive"))
    )
    (net (code "98") (name "Net-(R42-Pad2)") (class "Default")
      (node (ref "R42") (pin "2") (pinfunction "2_2") (pintype "passive"))
      (node (ref "SJ21") (pin "1") (pinfunction "1_1") (pintype "passive"))
    )
    (net (code "99") (name "Net-(S2-NO_1)") (class "Default")
      (node (ref "R11") (pin "1") (pinfunction "1_1") (pintype "passive"))
      (node (ref "R13") (pin "2") (pinfunction "2_2") (pintype "passive"))
      (node (ref "S2") (pin "1") (pinfunction "NO_1_1") (pintype "bidirectional"))
      (node (ref "S2") (pin "2") (pinfunction "NO_2_2") (pintype "bidirectional"))
    )
    (net (code "100") (name "Net-(S4-NO1)") (class "Default")
      (node (ref "LED1") (pin "A") (pinfunction "A_A") (pintype "passive"))
      (node (ref "S4") (pin "1B") (pinfunction "NO1_1B") (pintype "passive"))
    )
    (net (code "101") (name "Net-(U1-XTAL1)") (class "Default")
      (node (ref "U1") (pin "8") (pinfunction "XTAL1_8") (pintype "bidirectional"))
      (node (ref "Y1") (pin "1") (pinfunction "1_1") (pintype "passive"))
    )
    (net (code "102") (name "Net-(U1-XTAL2)") (class "Default")
      (node (ref "U1") (pin "7") (pinfunction "XTAL2_7") (pintype "bidirectional"))
      (node (ref "Y1") (pin "3") (pinfunction "3_3") (pintype "passive"))
    )
    (net (code "103") (name "Net-(U2-SQW{slash}INT)") (class "Default")
      (node (ref "SJ1") (pin "2") (pinfunction "2_2") (pintype "passive"))
      (node (ref "U2") (pin "3") (pinfunction "SQW/INT_3") (pintype "bidirectional"))
    )
    (net (code "104") (name "Net-(U2-VBAT)") (class "Default")
      (node (ref "BAT1") (pin "+1") (pinfunction "V+_+1") (pintype "bidirectional"))
      (node (ref "BAT1") (pin "+2") (pinfunction "V+_+2") (pintype "bidirectional"))
      (node (ref "U2") (pin "6") (pinfunction "VBAT_6") (pintype "bidirectional"))
    )
    (net (code "105") (name "Net-(U3-GPIO.2_{slash}_TXT)") (class "Default")
      (node (ref "LED5") (pin "C") (pinfunction "C_C") (pintype "passive"))
      (node (ref "U3") (pin "20") (pinfunction "GPIO.2_/_TXT_20") (pintype "bidirectional"))
    )
    (net (code "106") (name "Net-(U3-GPIO.3_{slash}_RXT)") (class "Default")
      (node (ref "LED6") (pin "C") (pinfunction "C_C") (pintype "passive"))
      (node (ref "U3") (pin "19") (pinfunction "GPIO.3_/_RXT_19") (pintype "bidirectional"))
    )
    (net (code "107") (name "Net-(U3-RSTB)") (class "Default")
      (node (ref "R21") (pin "1") (pinfunction "1_1") (pintype "passive"))
      (node (ref "U3") (pin "9") (pinfunction "RSTB_9") (pintype "bidirectional"))
    )
    (net (code "108") (name "Net-(U3-VBUS)") (class "Default")
      (node (ref "R24") (pin "1") (pinfunction "1_1") (pintype "passive"))
      (node (ref "R25") (pin "2") (pinfunction "2_2") (pintype "passive"))
      (node (ref "U3") (pin "8") (pinfunction "VBUS_8") (pintype "bidirectional"))
    )
    (net (code "109") (name "Net-(U4-CE)") (class "Default")
      (node (ref "H10") (pin "1") (pinfunction "1_1") (pintype "passive"))
      (node (ref "R26") (pin "2") (pinfunction "2_2") (pintype "passive"))
      (node (ref "S1") (pin "COM1") (pinfunction "COM1_COM1") (pintype "bidirectional"))
      (node (ref "U4") (pin "3") (pinfunction "CE_3") (pintype "bidirectional"))
    )
    (net (code "110") (name "Net-(U6-CE)") (class "Default")
      (node (ref "SJ18") (pin "2") (pinfunction "2_2") (pintype "passive"))
      (node (ref "U6") (pin "3") (pinfunction "CE_3") (pintype "bidirectional"))
    )
    (net (code "111") (name "Net-(U8-LX)") (class "Default")
      (node (ref "L2") (pin "2") (pinfunction "2_2") (pintype "bidirectional"))
      (node (ref "U8") (pin "2") (pinfunction "LX_2") (pintype "bidirectional"))
    )
    (net (code "112") (name "Net-(U9-ILIM)") (class "Default")
      (node (ref "R41") (pin "2") (pinfunction "2_2") (pintype "passive"))
      (node (ref "R5") (pin "2") (pinfunction "2_2") (pintype "passive"))
      (node (ref "U9") (pin "12") (pinfunction "ILIM_12") (pintype "input"))
    )
    (net (code "113") (name "Net-(U9-IN)") (class "Default")
      (node (ref "C2") (pin "2") (pinfunction "2_2") (pintype "passive"))
      (node (ref "C33") (pin "2") (pinfunction "2_2") (pintype "passive"))
      (node (ref "D1") (pin "1") (pinfunction "1_1") (pintype "passive"))
      (node (ref "D2") (pin "1") (pinfunction "1_1") (pintype "passive"))
      (node (ref "U9") (pin "13") (pinfunction "IN_13") (pintype "power_in"))
    )
    (net (code "114") (name "Net-(U9-ISET)") (class "Default")
      (node (ref "R39") (pin "2") (pinfunction "2_2") (pintype "passive"))
      (node (ref "R40") (pin "2") (pinfunction "2_2") (pintype "passive"))
      (node (ref "U9") (pin "16") (pinfunction "ISET_16") (pintype "input"))
    )
    (net (code "115") (name "Net-(U9-TS)") (class "Default")
      (node (ref "R35") (pin "2") (pinfunction "2_2") (pintype "passive"))
      (node (ref "U9") (pin "1") (pinfunction "TS_1") (pintype "input"))
    )
    (net (code "116") (name "Net-(U9-~{CHG})") (class "Default")
      (node (ref "LED4") (pin "C") (pinfunction "C_C") (pintype "passive"))
      (node (ref "U9") (pin "9") (pinfunction "~{CHG}_9") (pintype "output"))
    )
    (net (code "117") (name "Net-(U10-FB)") (class "Default")
      (node (ref "R15") (pin "1") (pinfunction "1_1") (pintype "passive"))
      (node (ref "R19") (pin "2") (pinfunction "2_2") (pintype "passive"))
      (node (ref "R31") (pin "2") (pinfunction "2_2") (pintype "passive"))
      (node (ref "U10") (pin "4") (pinfunction "FB_4") (pintype "bidirectional"))
    )
    (net (code "118") (name "Net-(U10-SW1)") (class "Default")
      (node (ref "D7") (pin "2") (pinfunction "2_2") (pintype "passive"))
      (node (ref "L1") (pin "2") (pinfunction "2_2") (pintype "bidirectional"))
      (node (ref "U10") (pin "8") (pinfunction "SW1_8") (pintype "bidirectional"))
      (node (ref "U10") (pin "9") (pinfunction "SW2_9") (pintype "bidirectional"))
    )
    (net (code "119") (name "Net-(U13-VDD)") (class "Default")
      (node (ref "SJ22") (pin "2") (pinfunction "2_2") (pintype "passive"))
      (node (ref "U13") (pin "3") (pinfunction "VDD_3") (pintype "power_in"))
    )
    (net (code "120") (name "RESET") (class "Default")
      (node (ref "C14") (pin "1") (pinfunction "1_1") (pintype "passive"))
      (node (ref "C4") (pin "2") (pinfunction "2_2") (pintype "passive"))
      (node (ref "H4") (pin "P$5") (pinfunction "PIN5_P$5") (pintype "bidirectional"))
      (node (ref "R3") (pin "1") (pinfunction "1_1") (pintype "passive"))
      (node (ref "S3") (pin "3") (pinfunction "3_3") (pintype "passive"))
      (node (ref "S3") (pin "4") (pinfunction "4_4") (pintype "passive"))
      (node (ref "U1") (pin "4") (pinfunction "~{RESET}_4") (pintype "bidirectional"))
    )
    (net (code "121") (name "VUSB") (class "Default")
      (node (ref "D1") (pin "2") (pinfunction "2_2") (pintype "passive"))
      (node (ref "D3") (pin "2") (pinfunction "2_2") (pintype "passive"))
      (node (ref "D4") (pin "2") (pinfunction "2_2") (pintype "passive"))
      (node (ref "D5") (pin "2") (pinfunction "2_2") (pintype "passive"))
      (node (ref "D6") (pin "2") (pinfunction "2_2") (pintype "passive"))
      (node (ref "H3") (pin "4") (pinfunction "4_4") (pintype "passive"))
      (node (ref "J6") (pin "A4/B9") (pinfunction "VBUS_A4/B9") (pintype "power_in"))
      (node (ref "J6") (pin "B4/A9") (pinfunction "VBUS_B4/A9") (pintype "power_in"))
      (node (ref "Q1") (pin "1") (pinfunction "G_1") (pintype "passive"))
      (node (ref "Q2") (pin "1") (pinfunction "G_1") (pintype "passive"))
      (node (ref "Q3") (pin "1") (pinfunction "G_1") (pintype "passive"))
      (node (ref "R6") (pin "2") (pinfunction "2_2") (pintype "passive"))
      (node (ref "S4") (pin "2A") (pinfunction "COM2_2A") (pintype "passive"))
    )
    (net (code "122") (name "V_BATT") (class "Default")
      (node (ref "C26") (pin "2") (pinfunction "2_2") (pintype "passive"))
      (node (ref "C27") (pin "2") (pinfunction "2_2") (pintype "passive"))
      (node (ref "C28") (pin "2") (pinfunction "2_2") (pintype "passive"))
      (node (ref "H2") (pin "12") (pinfunction "12_12") (pintype "bidirectional"))
      (node (ref "Q1") (pin "3") (pinfunction "D_3") (pintype "passive"))
      (node (ref "Q2") (pin "3") (pinfunction "D_3") (pintype "passive"))
      (node (ref "Q3") (pin "3") (pinfunction "D_3") (pintype "passive"))
      (node (ref "SJ4") (pin "1") (pinfunction "1_1") (pintype "passive"))
      (node (ref "U9") (pin "10") (pinfunction "OUT_10") (pintype "output"))
      (node (ref "U9") (pin "11") (pinfunction "OUT_11") (pintype "output"))
      (node (ref "U9") (pin "5") (pinfunction "EN2_5") (pintype "input"))
    )
    (net (code "123") (name "V_SOLAR") (class "Default")
      (node (ref "D2") (pin "2") (pinfunction "2_2") (pintype "passive"))
      (node (ref "J3") (pin "1") (pinfunction "1_1") (pintype "bidirectional"))
      (node (ref "J4") (pin "1") (pinfunction "1_1") (pintype "bidirectional"))
    )
    (net (code "124") (name "unconnected-(H7-H8-DIO1-Pad19)") (class "Default")
      (node (ref "H7-H8") (pin "19") (pinfunction "DIO1_19") (pintype "bidirectional"))
    )
    (net (code "125") (name "unconnected-(H7-H8-DIO2-Pad18)") (class "Default")
      (node (ref "H7-H8") (pin "18") (pinfunction "DIO2_18") (pintype "bidirectional"))
    )
    (net (code "126") (name "unconnected-(H7-H8-DIO3-Pad17)") (class "Default")
      (node (ref "H7-H8") (pin "17") (pinfunction "DIO3_17") (pintype "bidirectional"))
    )
    (net (code "127") (name "unconnected-(H7-H8-DIO4-Pad11)") (class "Default")
      (node (ref "H7-H8") (pin "11") (pinfunction "DIO4_11") (pintype "bidirectional"))
    )
    (net (code "128") (name "unconnected-(H7-H8-DIO11-Pad7)") (class "Default")
      (node (ref "H7-H8") (pin "7") (pinfunction "DIO11_7") (pintype "bidirectional"))
    )
    (net (code "129") (name "unconnected-(H7-H8-DIO12-Pad4)") (class "Default")
      (node (ref "H7-H8") (pin "4") (pinfunction "DIO12_4") (pintype "bidirectional"))
    )
    (net (code "130") (name "unconnected-(H7-H8-RES-Pad8)") (class "Default")
      (node (ref "H7-H8") (pin "8") (pinfunction "RES_8") (pintype "bidirectional"))
    )
    (net (code "131") (name "unconnected-(H7-H8-RES-Pad14)") (class "Default")
      (node (ref "H7-H8") (pin "14") (pinfunction "RES_14") (pintype "bidirectional"))
    )
    (net (code "132") (name "unconnected-(H7-H8-RSSI-Pad6)") (class "Default")
      (node (ref "H7-H8") (pin "6") (pinfunction "RSSI_6") (pintype "bidirectional"))
    )
    (net (code "133") (name "unconnected-(J5-CDN-Pad9)") (class "Default")
      (node (ref "J5") (pin "9") (pinfunction "CDN_9") (pintype "bidirectional"))
    )
    (net (code "134") (name "unconnected-(J5-DATA1-Pad8)") (class "Default")
      (node (ref "J5") (pin "8") (pinfunction "DATA1_8") (pintype "bidirectional"))
    )
    (net (code "135") (name "unconnected-(J5-DATA2-Pad1)") (class "Default")
      (node (ref "J5") (pin "1") (pinfunction "DATA2_1") (pintype "bidirectional"))
    )
    (net (code "136") (name "unconnected-(J6-SBU1-PadA8)") (class "Default")
      (node (ref "J6") (pin "A8") (pinfunction "SBU1_A8") (pintype "bidirectional"))
    )
    (net (code "137") (name "unconnected-(J6-SBU2-PadB8)") (class "Default")
      (node (ref "J6") (pin "B8") (pinfunction "SBU2_B8") (pintype "bidirectional"))
    )
    (net (code "138") (name "unconnected-(J7G-J-Pad7)") (class "Default")
      (node (ref "J7") (pin "7") (pinfunction "J_7") (pintype "passive"))
    )
    (net (code "139") (name "unconnected-(J7H-J-Pad8)") (class "Default")
      (node (ref "J7") (pin "8") (pinfunction "J_8") (pintype "passive"))
    )
    (net (code "140") (name "unconnected-(JP1-Pad1)") (class "Default")
      (node (ref "JP1") (pin "1") (pinfunction "1_1") (pintype "bidirectional"))
    )
    (net (code "141") (name "unconnected-(JP1-Pad3)") (class "Default")
      (node (ref "JP1") (pin "3") (pinfunction "3_3") (pintype "bidirectional"))
    )
    (net (code "142") (name "unconnected-(JP2-Pad1)") (class "Default")
      (node (ref "JP2") (pin "1") (pinfunction "1_1") (pintype "bidirectional"))
    )
    (net (code "143") (name "unconnected-(JP2-Pad3)") (class "Default")
      (node (ref "JP2") (pin "3") (pinfunction "3_3") (pintype "bidirectional"))
    )
    (net (code "144") (name "unconnected-(JP3-Pad1)") (class "Default")
      (node (ref "JP3") (pin "1") (pinfunction "1_1") (pintype "bidirectional"))
    )
    (net (code "145") (name "unconnected-(JP3-Pad3)") (class "Default")
      (node (ref "JP3") (pin "3") (pinfunction "3_3") (pintype "bidirectional"))
    )
    (net (code "146") (name "unconnected-(JP4-Pad1)") (class "Default")
      (node (ref "JP4") (pin "1") (pinfunction "1_1") (pintype "bidirectional"))
    )
    (net (code "147") (name "unconnected-(JP4-Pad3)") (class "Default")
      (node (ref "JP4") (pin "3") (pinfunction "3_3") (pintype "bidirectional"))
    )
    (net (code "148") (name "unconnected-(JP5-Pad1)") (class "Default")
      (node (ref "JP5") (pin "1") (pinfunction "1_1") (pintype "bidirectional"))
    )
    (net (code "149") (name "unconnected-(JP5-Pad3)") (class "Default")
      (node (ref "JP5") (pin "3") (pinfunction "3_3") (pintype "bidirectional"))
    )
    (net (code "150") (name "unconnected-(S1-PadCH1B)") (class "Default")
      (node (ref "S1") (pin "CH1B") (pinfunction "CH1B_CH1B") (pintype "bidirectional"))
    )
    (net (code "151") (name "unconnected-(S1-PadCH2B)") (class "Default")
      (node (ref "S1") (pin "CH2B") (pinfunction "CH2B_CH2B") (pintype "bidirectional"))
    )
    (net (code "152") (name "unconnected-(U2-32KHZ-Pad1)") (class "Default")
      (node (ref "U2") (pin "1") (pinfunction "32KHZ_1") (pintype "bidirectional"))
    )
    (net (code "153") (name "unconnected-(U2-{slash}RST-Pad4)") (class "Default")
      (node (ref "U2") (pin "4") (pinfunction "/RST_4") (pintype "bidirectional"))
    )
    (net (code "154") (name "unconnected-(U3-CTS-Pad15)") (class "Default")
      (node (ref "U3") (pin "15") (pinfunction "CTS_15") (pintype "bidirectional"))
    )
    (net (code "155") (name "unconnected-(U3-GPIO.0_{slash}_CLK-Pad2)") (class "Default")
      (node (ref "U3") (pin "2") (pinfunction "GPIO.0_/_CLK_2") (pintype "bidirectional"))
    )
    (net (code "156") (name "unconnected-(U3-GPIO.1_{slash}_RS485-Pad1)") (class "Default")
      (node (ref "U3") (pin "1") (pinfunction "GPIO.1_/_RS485_1") (pintype "bidirectional"))
    )
    (net (code "157") (name "unconnected-(U3-NC-Pad10)") (class "Default")
      (node (ref "U3") (pin "10") (pinfunction "NC_10") (pintype "no_connect"))
    )
    (net (code "158") (name "unconnected-(U3-SUSPEND-Pad14)") (class "Default")
      (node (ref "U3") (pin "14") (pinfunction "SUSPEND_14") (pintype "bidirectional"))
    )
    (net (code "159") (name "unconnected-(U3-SUSPENDB-Pad11)") (class "Default")
      (node (ref "U3") (pin "11") (pinfunction "SUSPENDB_11") (pintype "bidirectional"))
    )
    (net (code "160") (name "unconnected-(U3-WAKEUP-Pad13)") (class "Default")
      (node (ref "U3") (pin "13") (pinfunction "WAKEUP_13") (pintype "bidirectional"))
    )
    (net (code "161") (name "unconnected-(U4-NC-Pad4)") (class "Default")
      (node (ref "U4") (pin "4") (pinfunction "NC_4") (pintype "no_connect"))
    )
    (net (code "162") (name "unconnected-(U5-NC-Pad4)") (class "Default")
      (node (ref "U5") (pin "4") (pinfunction "NC_4") (pintype "no_connect"))
    )
    (net (code "163") (name "unconnected-(U6-NC-Pad4)") (class "Default")
      (node (ref "U6") (pin "4") (pinfunction "NC_4") (pintype "no_connect"))
    )
    (net (code "164") (name "unconnected-(U9-ITERM-Pad15)") (class "Default")
      (node (ref "U9") (pin "15") (pinfunction "ITERM_15") (pintype "input"))
    )
    (net (code "165") (name "unconnected-(U9-~{PGOOD}-Pad7)") (class "Default")
      (node (ref "U9") (pin "7") (pinfunction "~{PGOOD}_7") (pintype "output"))
    )
    (net (code "166") (name "unconnected-(U13-NC-Pad5)") (class "Default")
      (node (ref "U13") (pin "5") (pinfunction "NC_5") (pintype "no_connect"))
    )
  )
)
